# Fastino_FPGA_LVDS.net
KiCad netlist of a schematic drawn in Altium Designer
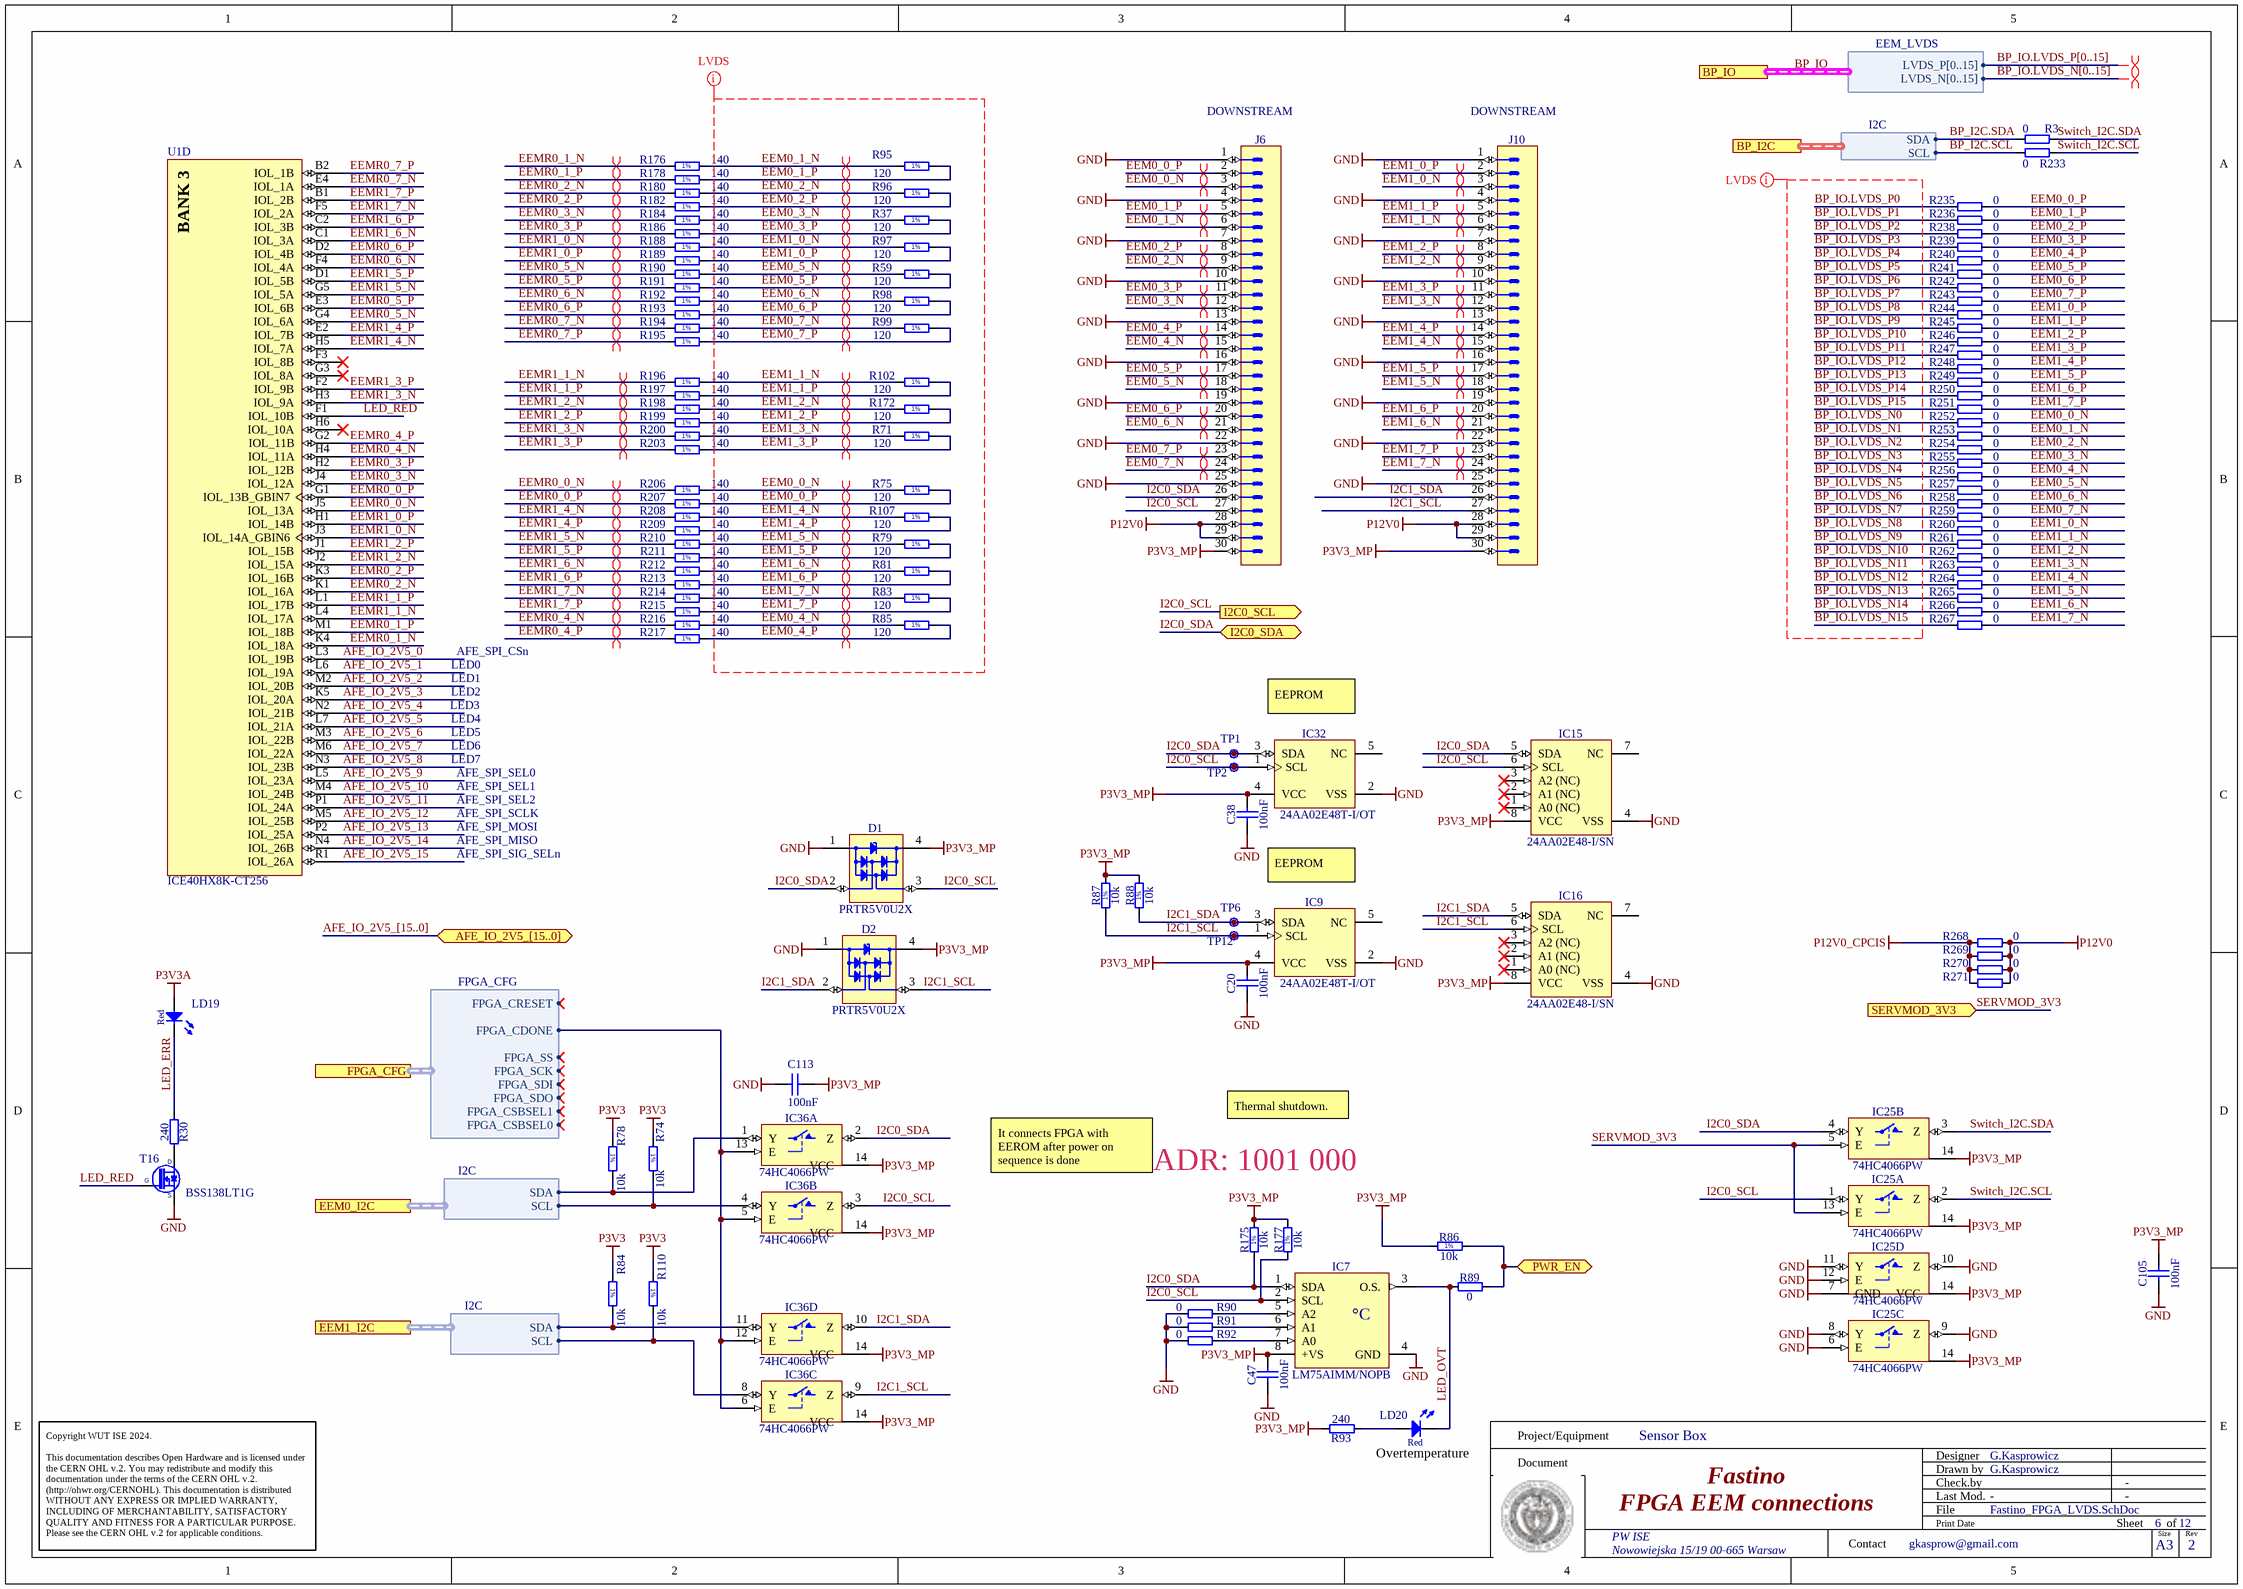
[diagram p0: Fastino_FPGA_LVDS.SchDoc]

(export (version "E")
  (design (tool "Eeschema 10.0.6"))
  (components
    (comp (ref "C20")
      (value "100nF")
      (footprint "CAPC1005X55N")
      (description "Non-polarised capacitor")
      (fields
        (field (name "PART NUMBER") "CC0402_100NF_16V_10%_X5R")
        (field (name "VOLTAGE") "16V")
        (field (name "AUTHOR") "CERN DEM JLC")
      )
      (libsource (lib "Capacitors") (part "Capacitor - non polarized"))
    )
    (comp (ref "C38")
      (value "100nF")
      (footprint "CAPC1005X55N")
      (description "Non-polarised capacitor")
      (fields
        (field (name "PART NUMBER") "CC0402_100NF_16V_10%_X5R")
        (field (name "VOLTAGE") "16V")
        (field (name "AUTHOR") "CERN DEM JLC")
      )
      (libsource (lib "Capacitors") (part "Capacitor - non polarized"))
    )
    (comp (ref "C47")
      (value "100nF")
      (footprint "CAPC1005X55N")
      (description "Non-polarised capacitor")
      (fields
        (field (name "PART NUMBER") "CC0402_100NF_16V_10%_X5R")
        (field (name "VOLTAGE") "16V")
        (field (name "AUTHOR") "CERN DEM JLC")
      )
      (libsource (lib "Capacitors") (part "Capacitor - non polarized"))
    )
    (comp (ref "C105")
      (value "100nF")
      (footprint "CAPC1005X55N")
      (description "Non-polarised capacitor")
      (fields
        (field (name "PART NUMBER") "CC0402_100NF_16V_10%_X5R")
        (field (name "VOLTAGE") "16V")
        (field (name "AUTHOR") "CERN DEM JLC")
      )
      (libsource (lib "Capacitors") (part "Capacitor - non polarized"))
    )
    (comp (ref "C113")
      (value "100nF")
      (footprint "CAPC1005X55N")
      (description "Non-polarised capacitor")
      (fields
        (field (name "PART NUMBER") "CC0402_100NF_16V_10%_X5R")
        (field (name "VOLTAGE") "16V")
        (field (name "AUTHOR") "CERN DEM JLC")
      )
      (libsource (lib "Capacitors") (part "Capacitor - non polarized"))
    )
    (comp (ref "D1")
      (value "PRTR5V0U2X")
      (footprint "SOT190P230X110-4N")
      (description "Ultra Low Capacitance Double Rail-to-Rail ESD Protection Diode")
      (fields
        (field (name "VOLTAGE") "5.5V")
        (field (name "MANUFACTURER") "NXP SEMICONDUCTORS")
        (field (name "AUTHOR") "CERN DEM JLC")
      )
      (libsource (lib "ICs And Semiconductors") (part "PRTR5V0U2X"))
    )
    (comp (ref "D2")
      (value "PRTR5V0U2X")
      (footprint "SOT190P230X110-4N")
      (description "Ultra Low Capacitance Double Rail-to-Rail ESD Protection Diode")
      (fields
        (field (name "VOLTAGE") "5.5V")
        (field (name "MANUFACTURER") "NXP SEMICONDUCTORS")
        (field (name "AUTHOR") "CERN DEM JLC")
      )
      (libsource (lib "ICs And Semiconductors") (part "PRTR5V0U2X"))
    )
    (comp (ref "IC7")
      (value "LM75AIMM/NOPB")
      (footprint "SOP65P490X109-8N")
      (description "Digital Temperature Sensor and Thermal Watchdog with Two-Wire Interface")
      (fields (field (name "MANUFACTURER") "TEXAS INSTRUMENTS") (field (name "AUTHOR") "CERN DEM JLC"))
      (libsource (lib "ICs And Semiconductors") (part "LM75"))
    )
    (comp (ref "IC9")
      (value "24AA02E48T-I/OT")
      (footprint "SOT95P280X145-5N")
      (description "1.7V-5.5V, 2K I2C Serial EEPROM With EUI-48 Node Identity")
      (fields (field (name "MANUFACTURER") "MICROCHIP TECHNOLOGY") (field (name "AUTHOR") "CERN DEM MR"))
      (libsource (lib "ICs And Semiconductors") (part "24AA02E48T-I/OT"))
    )
    (comp (ref "IC15")
      (value "24AA02E48-I/SN")
      (footprint "SOIC127P600X175-8N")
      (description "1.7V-5.5V, 2K I2C™ Serial EEPROMs with EUI-48™ Node Identity")
      (fields (field (name "MANUFACTURER") "MICROCHIP TECHNOLOGY") (field (name "AUTHOR") "CERN DEM MR"))
      (libsource (lib "ICS-logic") (part "MEM_24AA02E48-I/SN"))
    )
    (comp (ref "IC16")
      (value "24AA02E48-I/SN")
      (footprint "SOIC127P600X175-8N")
      (description "1.7V-5.5V, 2K I2C™ Serial EEPROMs with EUI-48™ Node Identity")
      (fields (field (name "MANUFACTURER") "MICROCHIP TECHNOLOGY") (field (name "AUTHOR") "CERN DEM MR"))
      (libsource (lib "ICS-logic") (part "MEM_24AA02E48-I/SN"))
    )
    (comp (ref "IC25")
      (value "74HC4066PW")
      (footprint "SOP65P640X110-14N")
      (fields (field (name "MANUFACTURER") "NXP SEMICONDUCTORS") (field (name "AUTHOR") "CERN DEM JLC"))
      (libsource (lib "ICs And Semiconductors") (part "4066"))
    )
    (comp (ref "IC32")
      (value "24AA02E48T-I/OT")
      (footprint "SOT95P280X145-5N")
      (description "1.7V-5.5V, 2K I2C Serial EEPROM With EUI-48 Node Identity")
      (fields (field (name "MANUFACTURER") "MICROCHIP TECHNOLOGY") (field (name "AUTHOR") "CERN DEM MR"))
      (libsource (lib "ICs And Semiconductors") (part "24AA02E48T-I/OT"))
    )
    (comp (ref "IC36")
      (value "74HC4066PW")
      (footprint "SOP65P640X110-14N")
      (fields (field (name "MANUFACTURER") "NXP SEMICONDUCTORS") (field (name "AUTHOR") "CERN DEM JLC"))
      (libsource (lib "ICs And Semiconductors") (part "4066"))
    )
    (comp (ref "J6")
      (value "~")
      (footprint "3M_N2530-6002RB")
      (description "Connector 30 Male")
      (fields
        (field (name "PART NUMBER") "3M_N2530-6002RB")
        (field (name "MANUFACTURER") "3M")
        (field (name "AUTHOR") "CERN DEM JLC")
      )
      (libsource (lib "Connectors") (part "Connector 30 Male"))
    )
    (comp (ref "J10")
      (value "~")
      (footprint "3M_N2530-6002RB")
      (description "Connector 30 Male")
      (fields
        (field (name "PART NUMBER") "3M_N2530-6002RB")
        (field (name "MANUFACTURER") "3M")
        (field (name "AUTHOR") "CERN DEM JLC")
      )
      (libsource (lib "Connectors") (part "Connector 30 Male"))
    )
    (comp (ref "LD19")
      (value "Red")
      (footprint "LED_AVAGO_HSMC-C120")
      (description "LED Red 1C 2A")
      (fields
        (field (name "PART NUMBER") "LED_AVAGO_HSMC-C120")
        (field (name "MANUFACTURER") "AVAGO TECHNOLOGIES")
        (field (name "AUTHOR") "CERN DEM JMW")
      )
      (libsource (lib "ICs And Semiconductors") (part "LED Red 1C 2A"))
    )
    (comp (ref "LD20")
      (value "Red")
      (footprint "LED_AVAGO_HSMC-C120")
      (description "LED Red 1C 2A")
      (fields
        (field (name "PART NUMBER") "LED_AVAGO_HSMC-C120")
        (field (name "MANUFACTURER") "AVAGO TECHNOLOGIES")
        (field (name "AUTHOR") "CERN DEM JMW")
      )
      (libsource (lib "ICs And Semiconductors") (part "LED Red 1C 2A"))
    )
    (comp (ref "R3")
      (value "0")
      (footprint "RESC1005X40N")
      (description "Resistor")
      (fields
        (field (name "PART NUMBER") "R0402_0R_JUMPER")
        (field (name "MANUFACTURER") "GENERIC")
        (field (name "AUTHOR") "CERN DEM JLC")
      )
      (libsource (lib "Resistors") (part "Resistor"))
    )
    (comp (ref "R30")
      (value "240")
      (footprint "RESC1005X40N")
      (description "Resistor - 1%")
      (fields
        (field (name "PART NUMBER") "R0402_240R_1%_0.0625W_100PPM")
        (field (name "POWER") "0.0625W")
        (field (name "AUTHOR") "CERN DEM JLC")
      )
      (libsource (lib "") (part "Resistor - 1%_1"))
    )
    (comp (ref "R37")
      (value "120")
      (footprint "RESC1005X40N")
      (description "Resistor - 1%")
      (fields
        (field (name "PART NUMBER") "R0402_120R_1%_0.0625W_100PPM")
        (field (name "POWER") "0.0625W")
        (field (name "AUTHOR") "CERN DEM JLC")
      )
      (libsource (lib "") (part "Resistor - 1%_1"))
    )
    (comp (ref "R59")
      (value "120")
      (footprint "RESC1005X40N")
      (description "Resistor - 1%")
      (fields
        (field (name "PART NUMBER") "R0402_120R_1%_0.0625W_100PPM")
        (field (name "POWER") "0.0625W")
        (field (name "AUTHOR") "CERN DEM JLC")
      )
      (libsource (lib "") (part "Resistor - 1%_1"))
    )
    (comp (ref "R71")
      (value "120")
      (footprint "RESC1005X40N")
      (description "Resistor - 1%")
      (fields
        (field (name "PART NUMBER") "R0402_120R_1%_0.0625W_100PPM")
        (field (name "POWER") "0.0625W")
        (field (name "AUTHOR") "CERN DEM JLC")
      )
      (libsource (lib "") (part "Resistor - 1%_1"))
    )
    (comp (ref "R74")
      (value "10k")
      (footprint "RESC1005X40N")
      (description "Resistor - 1%")
      (fields
        (field (name "PART NUMBER") "R0402_10K_1%_0.0625W_100PPM")
        (field (name "POWER") "0.0625W")
        (field (name "AUTHOR") "CERN DEM JLC")
      )
      (libsource (lib "") (part "Resistor - 1%_1"))
    )
    (comp (ref "R75")
      (value "120")
      (footprint "RESC1005X40N")
      (description "Resistor - 1%")
      (fields
        (field (name "PART NUMBER") "R0402_120R_1%_0.0625W_100PPM")
        (field (name "POWER") "0.0625W")
        (field (name "AUTHOR") "CERN DEM JLC")
      )
      (libsource (lib "") (part "Resistor - 1%_1"))
    )
    (comp (ref "R78")
      (value "10k")
      (footprint "RESC1005X40N")
      (description "Resistor - 1%")
      (fields
        (field (name "PART NUMBER") "R0402_10K_1%_0.0625W_100PPM")
        (field (name "POWER") "0.0625W")
        (field (name "AUTHOR") "CERN DEM JLC")
      )
      (libsource (lib "") (part "Resistor - 1%_1"))
    )
    (comp (ref "R79")
      (value "120")
      (footprint "RESC1005X40N")
      (description "Resistor - 1%")
      (fields
        (field (name "PART NUMBER") "R0402_120R_1%_0.0625W_100PPM")
        (field (name "POWER") "0.0625W")
        (field (name "AUTHOR") "CERN DEM JLC")
      )
      (libsource (lib "") (part "Resistor - 1%_1"))
    )
    (comp (ref "R81")
      (value "120")
      (footprint "RESC1005X40N")
      (description "Resistor - 1%")
      (fields
        (field (name "PART NUMBER") "R0402_120R_1%_0.0625W_100PPM")
        (field (name "POWER") "0.0625W")
        (field (name "AUTHOR") "CERN DEM JLC")
      )
      (libsource (lib "") (part "Resistor - 1%_1"))
    )
    (comp (ref "R83")
      (value "120")
      (footprint "RESC1005X40N")
      (description "Resistor - 1%")
      (fields
        (field (name "PART NUMBER") "R0402_120R_1%_0.0625W_100PPM")
        (field (name "POWER") "0.0625W")
        (field (name "AUTHOR") "CERN DEM JLC")
      )
      (libsource (lib "") (part "Resistor - 1%_1"))
    )
    (comp (ref "R84")
      (value "10k")
      (footprint "RESC1005X40N")
      (description "Resistor - 1%")
      (fields
        (field (name "PART NUMBER") "R0402_10K_1%_0.0625W_100PPM")
        (field (name "POWER") "0.0625W")
        (field (name "AUTHOR") "CERN DEM JLC")
      )
      (libsource (lib "") (part "Resistor - 1%_1"))
    )
    (comp (ref "R85")
      (value "120")
      (footprint "RESC1005X40N")
      (description "Resistor - 1%")
      (fields
        (field (name "PART NUMBER") "R0402_120R_1%_0.0625W_100PPM")
        (field (name "POWER") "0.0625W")
        (field (name "AUTHOR") "CERN DEM JLC")
      )
      (libsource (lib "") (part "Resistor - 1%_1"))
    )
    (comp (ref "R86")
      (value "10k")
      (footprint "RESC1005X40N")
      (description "Resistor - 1%")
      (fields
        (field (name "PART NUMBER") "R0402_10K_1%_0.0625W_100PPM")
        (field (name "POWER") "0.0625W")
        (field (name "AUTHOR") "CERN DEM JLC")
      )
      (libsource (lib "") (part "Resistor - 1%_1"))
    )
    (comp (ref "R87")
      (value "10k")
      (footprint "RESC1005X40N")
      (description "Resistor - 1%")
      (fields
        (field (name "PART NUMBER") "R0402_10K_1%_0.0625W_100PPM")
        (field (name "POWER") "0.0625W")
        (field (name "AUTHOR") "CERN DEM JLC")
      )
      (libsource (lib "") (part "Resistor - 1%_1"))
    )
    (comp (ref "R88")
      (value "10k")
      (footprint "RESC1005X40N")
      (description "Resistor - 1%")
      (fields
        (field (name "PART NUMBER") "R0402_10K_1%_0.0625W_100PPM")
        (field (name "POWER") "0.0625W")
        (field (name "AUTHOR") "CERN DEM JLC")
      )
      (libsource (lib "") (part "Resistor - 1%_1"))
    )
    (comp (ref "R89")
      (value "0")
      (footprint "RESC1005X40N")
      (description "Resistor")
      (fields
        (field (name "PART NUMBER") "R0402_0R_JUMPER")
        (field (name "MANUFACTURER") "GENERIC")
        (field (name "AUTHOR") "CERN DEM JLC")
      )
      (libsource (lib "Resistors") (part "Resistor"))
    )
    (comp (ref "R90")
      (value "0")
      (footprint "RESC1005X40N")
      (description "Resistor")
      (fields
        (field (name "PART NUMBER") "R0402_0R_JUMPER")
        (field (name "MANUFACTURER") "GENERIC")
        (field (name "AUTHOR") "CERN DEM JLC")
      )
      (libsource (lib "Resistors") (part "Resistor"))
    )
    (comp (ref "R91")
      (value "0")
      (footprint "RESC1005X40N")
      (description "Resistor")
      (fields
        (field (name "PART NUMBER") "R0402_0R_JUMPER")
        (field (name "MANUFACTURER") "GENERIC")
        (field (name "AUTHOR") "CERN DEM JLC")
      )
      (libsource (lib "Resistors") (part "Resistor"))
    )
    (comp (ref "R92")
      (value "0")
      (footprint "RESC1005X40N")
      (description "Resistor")
      (fields
        (field (name "PART NUMBER") "R0402_0R_JUMPER")
        (field (name "MANUFACTURER") "GENERIC")
        (field (name "AUTHOR") "CERN DEM JLC")
      )
      (libsource (lib "Resistors") (part "Resistor"))
    )
    (comp (ref "R93")
      (value "240")
      (footprint "RESC1005X40N")
      (description "Resistor - 1%")
      (fields
        (field (name "PART NUMBER") "R0402_240R_1%_0.0625W_100PPM")
        (field (name "POWER") "0.0625W")
        (field (name "AUTHOR") "CERN DEM JLC")
      )
      (libsource (lib "") (part "Resistor - 1%_1"))
    )
    (comp (ref "R95")
      (value "120")
      (footprint "RESC1005X40N")
      (description "Resistor - 1%")
      (fields
        (field (name "PART NUMBER") "R0402_120R_1%_0.0625W_100PPM")
        (field (name "POWER") "0.0625W")
        (field (name "AUTHOR") "CERN DEM JLC")
      )
      (libsource (lib "") (part "Resistor - 1%_1"))
    )
    (comp (ref "R96")
      (value "120")
      (footprint "RESC1005X40N")
      (description "Resistor - 1%")
      (fields
        (field (name "PART NUMBER") "R0402_120R_1%_0.0625W_100PPM")
        (field (name "POWER") "0.0625W")
        (field (name "AUTHOR") "CERN DEM JLC")
      )
      (libsource (lib "") (part "Resistor - 1%_1"))
    )
    (comp (ref "R97")
      (value "120")
      (footprint "RESC1005X40N")
      (description "Resistor - 1%")
      (fields
        (field (name "PART NUMBER") "R0402_120R_1%_0.0625W_100PPM")
        (field (name "POWER") "0.0625W")
        (field (name "AUTHOR") "CERN DEM JLC")
      )
      (libsource (lib "") (part "Resistor - 1%_1"))
    )
    (comp (ref "R98")
      (value "120")
      (footprint "RESC1005X40N")
      (description "Resistor - 1%")
      (fields
        (field (name "PART NUMBER") "R0402_120R_1%_0.0625W_100PPM")
        (field (name "POWER") "0.0625W")
        (field (name "AUTHOR") "CERN DEM JLC")
      )
      (libsource (lib "") (part "Resistor - 1%_1"))
    )
    (comp (ref "R99")
      (value "120")
      (footprint "RESC1005X40N")
      (description "Resistor - 1%")
      (fields
        (field (name "PART NUMBER") "R0402_120R_1%_0.0625W_100PPM")
        (field (name "POWER") "0.0625W")
        (field (name "AUTHOR") "CERN DEM JLC")
      )
      (libsource (lib "") (part "Resistor - 1%_1"))
    )
    (comp (ref "R102")
      (value "120")
      (footprint "RESC1005X40N")
      (description "Resistor - 1%")
      (fields
        (field (name "PART NUMBER") "R0402_120R_1%_0.0625W_100PPM")
        (field (name "POWER") "0.0625W")
        (field (name "AUTHOR") "CERN DEM JLC")
      )
      (libsource (lib "") (part "Resistor - 1%_1"))
    )
    (comp (ref "R107")
      (value "120")
      (footprint "RESC1005X40N")
      (description "Resistor - 1%")
      (fields
        (field (name "PART NUMBER") "R0402_120R_1%_0.0625W_100PPM")
        (field (name "POWER") "0.0625W")
        (field (name "AUTHOR") "CERN DEM JLC")
      )
      (libsource (lib "") (part "Resistor - 1%_1"))
    )
    (comp (ref "R110")
      (value "10k")
      (footprint "RESC1005X40N")
      (description "Resistor - 1%")
      (fields
        (field (name "PART NUMBER") "R0402_10K_1%_0.0625W_100PPM")
        (field (name "POWER") "0.0625W")
        (field (name "AUTHOR") "CERN DEM JLC")
      )
      (libsource (lib "") (part "Resistor - 1%_1"))
    )
    (comp (ref "R172")
      (value "120")
      (footprint "RESC1005X40N")
      (description "Resistor - 1%")
      (fields
        (field (name "PART NUMBER") "R0402_120R_1%_0.0625W_100PPM")
        (field (name "POWER") "0.0625W")
        (field (name "AUTHOR") "CERN DEM JLC")
      )
      (libsource (lib "") (part "Resistor - 1%_1"))
    )
    (comp (ref "R175")
      (value "10k")
      (footprint "RESC1005X40N")
      (description "Resistor - 1%")
      (fields
        (field (name "PART NUMBER") "R0402_10K_1%_0.0625W_100PPM")
        (field (name "POWER") "0.0625W")
        (field (name "AUTHOR") "CERN DEM JLC")
      )
      (libsource (lib "") (part "Resistor - 1%_1"))
    )
    (comp (ref "R176")
      (value "140")
      (footprint "RESC0603X28N")
      (description "Resistor - 1%")
      (fields
        (field (name "PART NUMBER") "R0201_140R_1%_0.05W_200PPM")
        (field (name "POWER") "0.05W")
        (field (name "AUTHOR") "CERN DEM MR")
      )
      (libsource (lib "Resistors") (part "Resistor - 1%"))
    )
    (comp (ref "R177")
      (value "10k")
      (footprint "RESC1005X40N")
      (description "Resistor - 1%")
      (fields
        (field (name "PART NUMBER") "R0402_10K_1%_0.0625W_100PPM")
        (field (name "POWER") "0.0625W")
        (field (name "AUTHOR") "CERN DEM JLC")
      )
      (libsource (lib "") (part "Resistor - 1%_1"))
    )
    (comp (ref "R178")
      (value "140")
      (footprint "RESC0603X28N")
      (description "Resistor - 1%")
      (fields
        (field (name "PART NUMBER") "R0201_140R_1%_0.05W_200PPM")
        (field (name "POWER") "0.05W")
        (field (name "AUTHOR") "CERN DEM MR")
      )
      (libsource (lib "Resistors") (part "Resistor - 1%"))
    )
    (comp (ref "R180")
      (value "140")
      (footprint "RESC0603X28N")
      (description "Resistor - 1%")
      (fields
        (field (name "PART NUMBER") "R0201_140R_1%_0.05W_200PPM")
        (field (name "POWER") "0.05W")
        (field (name "AUTHOR") "CERN DEM MR")
      )
      (libsource (lib "Resistors") (part "Resistor - 1%"))
    )
    (comp (ref "R182")
      (value "140")
      (footprint "RESC0603X28N")
      (description "Resistor - 1%")
      (fields
        (field (name "PART NUMBER") "R0201_140R_1%_0.05W_200PPM")
        (field (name "POWER") "0.05W")
        (field (name "AUTHOR") "CERN DEM MR")
      )
      (libsource (lib "Resistors") (part "Resistor - 1%"))
    )
    (comp (ref "R184")
      (value "140")
      (footprint "RESC0603X28N")
      (description "Resistor - 1%")
      (fields
        (field (name "PART NUMBER") "R0201_140R_1%_0.05W_200PPM")
        (field (name "POWER") "0.05W")
        (field (name "AUTHOR") "CERN DEM MR")
      )
      (libsource (lib "Resistors") (part "Resistor - 1%"))
    )
    (comp (ref "R186")
      (value "140")
      (footprint "RESC0603X28N")
      (description "Resistor - 1%")
      (fields
        (field (name "PART NUMBER") "R0201_140R_1%_0.05W_200PPM")
        (field (name "POWER") "0.05W")
        (field (name "AUTHOR") "CERN DEM MR")
      )
      (libsource (lib "Resistors") (part "Resistor - 1%"))
    )
    (comp (ref "R188")
      (value "140")
      (footprint "RESC0603X28N")
      (description "Resistor - 1%")
      (fields
        (field (name "PART NUMBER") "R0201_140R_1%_0.05W_200PPM")
        (field (name "POWER") "0.05W")
        (field (name "AUTHOR") "CERN DEM MR")
      )
      (libsource (lib "Resistors") (part "Resistor - 1%"))
    )
    (comp (ref "R189")
      (value "140")
      (footprint "RESC0603X28N")
      (description "Resistor - 1%")
      (fields
        (field (name "PART NUMBER") "R0201_140R_1%_0.05W_200PPM")
        (field (name "POWER") "0.05W")
        (field (name "AUTHOR") "CERN DEM MR")
      )
      (libsource (lib "Resistors") (part "Resistor - 1%"))
    )
    (comp (ref "R190")
      (value "140")
      (footprint "RESC0603X28N")
      (description "Resistor - 1%")
      (fields
        (field (name "PART NUMBER") "R0201_140R_1%_0.05W_200PPM")
        (field (name "POWER") "0.05W")
        (field (name "AUTHOR") "CERN DEM MR")
      )
      (libsource (lib "Resistors") (part "Resistor - 1%"))
    )
    (comp (ref "R191")
      (value "140")
      (footprint "RESC0603X28N")
      (description "Resistor - 1%")
      (fields
        (field (name "PART NUMBER") "R0201_140R_1%_0.05W_200PPM")
        (field (name "POWER") "0.05W")
        (field (name "AUTHOR") "CERN DEM MR")
      )
      (libsource (lib "Resistors") (part "Resistor - 1%"))
    )
    (comp (ref "R192")
      (value "140")
      (footprint "RESC0603X28N")
      (description "Resistor - 1%")
      (fields
        (field (name "PART NUMBER") "R0201_140R_1%_0.05W_200PPM")
        (field (name "POWER") "0.05W")
        (field (name "AUTHOR") "CERN DEM MR")
      )
      (libsource (lib "Resistors") (part "Resistor - 1%"))
    )
    (comp (ref "R193")
      (value "140")
      (footprint "RESC0603X28N")
      (description "Resistor - 1%")
      (fields
        (field (name "PART NUMBER") "R0201_140R_1%_0.05W_200PPM")
        (field (name "POWER") "0.05W")
        (field (name "AUTHOR") "CERN DEM MR")
      )
      (libsource (lib "Resistors") (part "Resistor - 1%"))
    )
    (comp (ref "R194")
      (value "140")
      (footprint "RESC0603X28N")
      (description "Resistor - 1%")
      (fields
        (field (name "PART NUMBER") "R0201_140R_1%_0.05W_200PPM")
        (field (name "POWER") "0.05W")
        (field (name "AUTHOR") "CERN DEM MR")
      )
      (libsource (lib "Resistors") (part "Resistor - 1%"))
    )
    (comp (ref "R195")
      (value "140")
      (footprint "RESC0603X28N")
      (description "Resistor - 1%")
      (fields
        (field (name "PART NUMBER") "R0201_140R_1%_0.05W_200PPM")
        (field (name "POWER") "0.05W")
        (field (name "AUTHOR") "CERN DEM MR")
      )
      (libsource (lib "Resistors") (part "Resistor - 1%"))
    )
    (comp (ref "R196")
      (value "140")
      (footprint "RESC0603X28N")
      (description "Resistor - 1%")
      (fields
        (field (name "PART NUMBER") "R0201_140R_1%_0.05W_200PPM")
        (field (name "POWER") "0.05W")
        (field (name "AUTHOR") "CERN DEM MR")
      )
      (libsource (lib "Resistors") (part "Resistor - 1%"))
    )
    (comp (ref "R197")
      (value "140")
      (footprint "RESC0603X28N")
      (description "Resistor - 1%")
      (fields
        (field (name "PART NUMBER") "R0201_140R_1%_0.05W_200PPM")
        (field (name "POWER") "0.05W")
        (field (name "AUTHOR") "CERN DEM MR")
      )
      (libsource (lib "Resistors") (part "Resistor - 1%"))
    )
    (comp (ref "R198")
      (value "140")
      (footprint "RESC0603X28N")
      (description "Resistor - 1%")
      (fields
        (field (name "PART NUMBER") "R0201_140R_1%_0.05W_200PPM")
        (field (name "POWER") "0.05W")
        (field (name "AUTHOR") "CERN DEM MR")
      )
      (libsource (lib "Resistors") (part "Resistor - 1%"))
    )
    (comp (ref "R199")
      (value "140")
      (footprint "RESC0603X28N")
      (description "Resistor - 1%")
      (fields
        (field (name "PART NUMBER") "R0201_140R_1%_0.05W_200PPM")
        (field (name "POWER") "0.05W")
        (field (name "AUTHOR") "CERN DEM MR")
      )
      (libsource (lib "Resistors") (part "Resistor - 1%"))
    )
    (comp (ref "R200")
      (value "140")
      (footprint "RESC0603X28N")
      (description "Resistor - 1%")
      (fields
        (field (name "PART NUMBER") "R0201_140R_1%_0.05W_200PPM")
        (field (name "POWER") "0.05W")
        (field (name "AUTHOR") "CERN DEM MR")
      )
      (libsource (lib "Resistors") (part "Resistor - 1%"))
    )
    (comp (ref "R203")
      (value "140")
      (footprint "RESC0603X28N")
      (description "Resistor - 1%")
      (fields
        (field (name "PART NUMBER") "R0201_140R_1%_0.05W_200PPM")
        (field (name "POWER") "0.05W")
        (field (name "AUTHOR") "CERN DEM MR")
      )
      (libsource (lib "Resistors") (part "Resistor - 1%"))
    )
    (comp (ref "R206")
      (value "140")
      (footprint "RESC0603X28N")
      (description "Resistor - 1%")
      (fields
        (field (name "PART NUMBER") "R0201_140R_1%_0.05W_200PPM")
        (field (name "POWER") "0.05W")
        (field (name "AUTHOR") "CERN DEM MR")
      )
      (libsource (lib "Resistors") (part "Resistor - 1%"))
    )
    (comp (ref "R207")
      (value "140")
      (footprint "RESC0603X28N")
      (description "Resistor - 1%")
      (fields
        (field (name "PART NUMBER") "R0201_140R_1%_0.05W_200PPM")
        (field (name "POWER") "0.05W")
        (field (name "AUTHOR") "CERN DEM MR")
      )
      (libsource (lib "Resistors") (part "Resistor - 1%"))
    )
    (comp (ref "R208")
      (value "140")
      (footprint "RESC0603X28N")
      (description "Resistor - 1%")
      (fields
        (field (name "PART NUMBER") "R0201_140R_1%_0.05W_200PPM")
        (field (name "POWER") "0.05W")
        (field (name "AUTHOR") "CERN DEM MR")
      )
      (libsource (lib "Resistors") (part "Resistor - 1%"))
    )
    (comp (ref "R209")
      (value "140")
      (footprint "RESC0603X28N")
      (description "Resistor - 1%")
      (fields
        (field (name "PART NUMBER") "R0201_140R_1%_0.05W_200PPM")
        (field (name "POWER") "0.05W")
        (field (name "AUTHOR") "CERN DEM MR")
      )
      (libsource (lib "Resistors") (part "Resistor - 1%"))
    )
    (comp (ref "R210")
      (value "140")
      (footprint "RESC0603X28N")
      (description "Resistor - 1%")
      (fields
        (field (name "PART NUMBER") "R0201_140R_1%_0.05W_200PPM")
        (field (name "POWER") "0.05W")
        (field (name "AUTHOR") "CERN DEM MR")
      )
      (libsource (lib "Resistors") (part "Resistor - 1%"))
    )
    (comp (ref "R211")
      (value "140")
      (footprint "RESC0603X28N")
      (description "Resistor - 1%")
      (fields
        (field (name "PART NUMBER") "R0201_140R_1%_0.05W_200PPM")
        (field (name "POWER") "0.05W")
        (field (name "AUTHOR") "CERN DEM MR")
      )
      (libsource (lib "Resistors") (part "Resistor - 1%"))
    )
    (comp (ref "R212")
      (value "140")
      (footprint "RESC0603X28N")
      (description "Resistor - 1%")
      (fields
        (field (name "PART NUMBER") "R0201_140R_1%_0.05W_200PPM")
        (field (name "POWER") "0.05W")
        (field (name "AUTHOR") "CERN DEM MR")
      )
      (libsource (lib "Resistors") (part "Resistor - 1%"))
    )
    (comp (ref "R213")
      (value "140")
      (footprint "RESC0603X28N")
      (description "Resistor - 1%")
      (fields
        (field (name "PART NUMBER") "R0201_140R_1%_0.05W_200PPM")
        (field (name "POWER") "0.05W")
        (field (name "AUTHOR") "CERN DEM MR")
      )
      (libsource (lib "Resistors") (part "Resistor - 1%"))
    )
    (comp (ref "R214")
      (value "140")
      (footprint "RESC0603X28N")
      (description "Resistor - 1%")
      (fields
        (field (name "PART NUMBER") "R0201_140R_1%_0.05W_200PPM")
        (field (name "POWER") "0.05W")
        (field (name "AUTHOR") "CERN DEM MR")
      )
      (libsource (lib "Resistors") (part "Resistor - 1%"))
    )
    (comp (ref "R215")
      (value "140")
      (footprint "RESC0603X28N")
      (description "Resistor - 1%")
      (fields
        (field (name "PART NUMBER") "R0201_140R_1%_0.05W_200PPM")
        (field (name "POWER") "0.05W")
        (field (name "AUTHOR") "CERN DEM MR")
      )
      (libsource (lib "Resistors") (part "Resistor - 1%"))
    )
    (comp (ref "R216")
      (value "140")
      (footprint "RESC0603X28N")
      (description "Resistor - 1%")
      (fields
        (field (name "PART NUMBER") "R0201_140R_1%_0.05W_200PPM")
        (field (name "POWER") "0.05W")
        (field (name "AUTHOR") "CERN DEM MR")
      )
      (libsource (lib "Resistors") (part "Resistor - 1%"))
    )
    (comp (ref "R217")
      (value "140")
      (footprint "RESC0603X28N")
      (description "Resistor - 1%")
      (fields
        (field (name "PART NUMBER") "R0201_140R_1%_0.05W_200PPM")
        (field (name "POWER") "0.05W")
        (field (name "AUTHOR") "CERN DEM MR")
      )
      (libsource (lib "Resistors") (part "Resistor - 1%"))
    )
    (comp (ref "R233")
      (value "0")
      (footprint "RESC1005X40N")
      (description "Resistor")
      (fields
        (field (name "PART NUMBER") "R0402_0R_JUMPER")
        (field (name "MANUFACTURER") "GENERIC")
        (field (name "AUTHOR") "CERN DEM JLC")
      )
      (libsource (lib "Resistors") (part "Resistor"))
    )
    (comp (ref "R235")
      (value "0")
      (footprint "RESC1005X40N")
      (description "Resistor")
      (fields
        (field (name "PART NUMBER") "R0402_0R_JUMPER")
        (field (name "MANUFACTURER") "GENERIC")
        (field (name "AUTHOR") "CERN DEM JLC")
      )
      (libsource (lib "Resistors") (part "Resistor"))
    )
    (comp (ref "R236")
      (value "0")
      (footprint "RESC1005X40N")
      (description "Resistor")
      (fields
        (field (name "PART NUMBER") "R0402_0R_JUMPER")
        (field (name "MANUFACTURER") "GENERIC")
        (field (name "AUTHOR") "CERN DEM JLC")
      )
      (libsource (lib "Resistors") (part "Resistor"))
    )
    (comp (ref "R238")
      (value "0")
      (footprint "RESC1005X40N")
      (description "Resistor")
      (fields
        (field (name "PART NUMBER") "R0402_0R_JUMPER")
        (field (name "MANUFACTURER") "GENERIC")
        (field (name "AUTHOR") "CERN DEM JLC")
      )
      (libsource (lib "Resistors") (part "Resistor"))
    )
    (comp (ref "R239")
      (value "0")
      (footprint "RESC1005X40N")
      (description "Resistor")
      (fields
        (field (name "PART NUMBER") "R0402_0R_JUMPER")
        (field (name "MANUFACTURER") "GENERIC")
        (field (name "AUTHOR") "CERN DEM JLC")
      )
      (libsource (lib "Resistors") (part "Resistor"))
    )
    (comp (ref "R240")
      (value "0")
      (footprint "RESC1005X40N")
      (description "Resistor")
      (fields
        (field (name "PART NUMBER") "R0402_0R_JUMPER")
        (field (name "MANUFACTURER") "GENERIC")
        (field (name "AUTHOR") "CERN DEM JLC")
      )
      (libsource (lib "Resistors") (part "Resistor"))
    )
    (comp (ref "R241")
      (value "0")
      (footprint "RESC1005X40N")
      (description "Resistor")
      (fields
        (field (name "PART NUMBER") "R0402_0R_JUMPER")
        (field (name "MANUFACTURER") "GENERIC")
        (field (name "AUTHOR") "CERN DEM JLC")
      )
      (libsource (lib "Resistors") (part "Resistor"))
    )
    (comp (ref "R242")
      (value "0")
      (footprint "RESC1005X40N")
      (description "Resistor")
      (fields
        (field (name "PART NUMBER") "R0402_0R_JUMPER")
        (field (name "MANUFACTURER") "GENERIC")
        (field (name "AUTHOR") "CERN DEM JLC")
      )
      (libsource (lib "Resistors") (part "Resistor"))
    )
    (comp (ref "R243")
      (value "0")
      (footprint "RESC1005X40N")
      (description "Resistor")
      (fields
        (field (name "PART NUMBER") "R0402_0R_JUMPER")
        (field (name "MANUFACTURER") "GENERIC")
        (field (name "AUTHOR") "CERN DEM JLC")
      )
      (libsource (lib "Resistors") (part "Resistor"))
    )
    (comp (ref "R244")
      (value "0")
      (footprint "RESC1005X40N")
      (description "Resistor")
      (fields
        (field (name "PART NUMBER") "R0402_0R_JUMPER")
        (field (name "MANUFACTURER") "GENERIC")
        (field (name "AUTHOR") "CERN DEM JLC")
      )
      (libsource (lib "Resistors") (part "Resistor"))
    )
    (comp (ref "R245")
      (value "0")
      (footprint "RESC1005X40N")
      (description "Resistor")
      (fields
        (field (name "PART NUMBER") "R0402_0R_JUMPER")
        (field (name "MANUFACTURER") "GENERIC")
        (field (name "AUTHOR") "CERN DEM JLC")
      )
      (libsource (lib "Resistors") (part "Resistor"))
    )
    (comp (ref "R246")
      (value "0")
      (footprint "RESC1005X40N")
      (description "Resistor")
      (fields
        (field (name "PART NUMBER") "R0402_0R_JUMPER")
        (field (name "MANUFACTURER") "GENERIC")
        (field (name "AUTHOR") "CERN DEM JLC")
      )
      (libsource (lib "Resistors") (part "Resistor"))
    )
    (comp (ref "R247")
      (value "0")
      (footprint "RESC1005X40N")
      (description "Resistor")
      (fields
        (field (name "PART NUMBER") "R0402_0R_JUMPER")
        (field (name "MANUFACTURER") "GENERIC")
        (field (name "AUTHOR") "CERN DEM JLC")
      )
      (libsource (lib "Resistors") (part "Resistor"))
    )
    (comp (ref "R248")
      (value "0")
      (footprint "RESC1005X40N")
      (description "Resistor")
      (fields
        (field (name "PART NUMBER") "R0402_0R_JUMPER")
        (field (name "MANUFACTURER") "GENERIC")
        (field (name "AUTHOR") "CERN DEM JLC")
      )
      (libsource (lib "Resistors") (part "Resistor"))
    )
    (comp (ref "R249")
      (value "0")
      (footprint "RESC1005X40N")
      (description "Resistor")
      (fields
        (field (name "PART NUMBER") "R0402_0R_JUMPER")
        (field (name "MANUFACTURER") "GENERIC")
        (field (name "AUTHOR") "CERN DEM JLC")
      )
      (libsource (lib "Resistors") (part "Resistor"))
    )
    (comp (ref "R250")
      (value "0")
      (footprint "RESC1005X40N")
      (description "Resistor")
      (fields
        (field (name "PART NUMBER") "R0402_0R_JUMPER")
        (field (name "MANUFACTURER") "GENERIC")
        (field (name "AUTHOR") "CERN DEM JLC")
      )
      (libsource (lib "Resistors") (part "Resistor"))
    )
    (comp (ref "R251")
      (value "0")
      (footprint "RESC0603X28N")
      (description "Resistor")
      (fields
        (field (name "PART NUMBER") "R0201_0R_JUMPER")
        (field (name "MANUFACTURER") "GENERIC")
        (field (name "AUTHOR") "CERN DEM JLC")
      )
      (libsource (lib "Resistors") (part "Resistor"))
    )
    (comp (ref "R252")
      (value "0")
      (footprint "RESC1005X40N")
      (description "Resistor")
      (fields
        (field (name "PART NUMBER") "R0402_0R_JUMPER")
        (field (name "MANUFACTURER") "GENERIC")
        (field (name "AUTHOR") "CERN DEM JLC")
      )
      (libsource (lib "Resistors") (part "Resistor"))
    )
    (comp (ref "R253")
      (value "0")
      (footprint "RESC1005X40N")
      (description "Resistor")
      (fields
        (field (name "PART NUMBER") "R0402_0R_JUMPER")
        (field (name "MANUFACTURER") "GENERIC")
        (field (name "AUTHOR") "CERN DEM JLC")
      )
      (libsource (lib "Resistors") (part "Resistor"))
    )
    (comp (ref "R254")
      (value "0")
      (footprint "RESC1005X40N")
      (description "Resistor")
      (fields
        (field (name "PART NUMBER") "R0402_0R_JUMPER")
        (field (name "MANUFACTURER") "GENERIC")
        (field (name "AUTHOR") "CERN DEM JLC")
      )
      (libsource (lib "Resistors") (part "Resistor"))
    )
    (comp (ref "R255")
      (value "0")
      (footprint "RESC1005X40N")
      (description "Resistor")
      (fields
        (field (name "PART NUMBER") "R0402_0R_JUMPER")
        (field (name "MANUFACTURER") "GENERIC")
        (field (name "AUTHOR") "CERN DEM JLC")
      )
      (libsource (lib "Resistors") (part "Resistor"))
    )
    (comp (ref "R256")
      (value "0")
      (footprint "RESC1005X40N")
      (description "Resistor")
      (fields
        (field (name "PART NUMBER") "R0402_0R_JUMPER")
        (field (name "MANUFACTURER") "GENERIC")
        (field (name "AUTHOR") "CERN DEM JLC")
      )
      (libsource (lib "Resistors") (part "Resistor"))
    )
    (comp (ref "R257")
      (value "0")
      (footprint "RESC1005X40N")
      (description "Resistor")
      (fields
        (field (name "PART NUMBER") "R0402_0R_JUMPER")
        (field (name "MANUFACTURER") "GENERIC")
        (field (name "AUTHOR") "CERN DEM JLC")
      )
      (libsource (lib "Resistors") (part "Resistor"))
    )
    (comp (ref "R258")
      (value "0")
      (footprint "RESC1005X40N")
      (description "Resistor")
      (fields
        (field (name "PART NUMBER") "R0402_0R_JUMPER")
        (field (name "MANUFACTURER") "GENERIC")
        (field (name "AUTHOR") "CERN DEM JLC")
      )
      (libsource (lib "Resistors") (part "Resistor"))
    )
    (comp (ref "R259")
      (value "0")
      (footprint "RESC1005X40N")
      (description "Resistor")
      (fields
        (field (name "PART NUMBER") "R0402_0R_JUMPER")
        (field (name "MANUFACTURER") "GENERIC")
        (field (name "AUTHOR") "CERN DEM JLC")
      )
      (libsource (lib "Resistors") (part "Resistor"))
    )
    (comp (ref "R260")
      (value "0")
      (footprint "RESC1005X40N")
      (description "Resistor")
      (fields
        (field (name "PART NUMBER") "R0402_0R_JUMPER")
        (field (name "MANUFACTURER") "GENERIC")
        (field (name "AUTHOR") "CERN DEM JLC")
      )
      (libsource (lib "Resistors") (part "Resistor"))
    )
    (comp (ref "R261")
      (value "0")
      (footprint "RESC1005X40N")
      (description "Resistor")
      (fields
        (field (name "PART NUMBER") "R0402_0R_JUMPER")
        (field (name "MANUFACTURER") "GENERIC")
        (field (name "AUTHOR") "CERN DEM JLC")
      )
      (libsource (lib "Resistors") (part "Resistor"))
    )
    (comp (ref "R262")
      (value "0")
      (footprint "RESC1005X40N")
      (description "Resistor")
      (fields
        (field (name "PART NUMBER") "R0402_0R_JUMPER")
        (field (name "MANUFACTURER") "GENERIC")
        (field (name "AUTHOR") "CERN DEM JLC")
      )
      (libsource (lib "Resistors") (part "Resistor"))
    )
    (comp (ref "R263")
      (value "0")
      (footprint "RESC1005X40N")
      (description "Resistor")
      (fields
        (field (name "PART NUMBER") "R0402_0R_JUMPER")
        (field (name "MANUFACTURER") "GENERIC")
        (field (name "AUTHOR") "CERN DEM JLC")
      )
      (libsource (lib "Resistors") (part "Resistor"))
    )
    (comp (ref "R264")
      (value "0")
      (footprint "RESC1005X40N")
      (description "Resistor")
      (fields
        (field (name "PART NUMBER") "R0402_0R_JUMPER")
        (field (name "MANUFACTURER") "GENERIC")
        (field (name "AUTHOR") "CERN DEM JLC")
      )
      (libsource (lib "Resistors") (part "Resistor"))
    )
    (comp (ref "R265")
      (value "0")
      (footprint "RESC1005X40N")
      (description "Resistor")
      (fields
        (field (name "PART NUMBER") "R0402_0R_JUMPER")
        (field (name "MANUFACTURER") "GENERIC")
        (field (name "AUTHOR") "CERN DEM JLC")
      )
      (libsource (lib "Resistors") (part "Resistor"))
    )
    (comp (ref "R266")
      (value "0")
      (footprint "RESC1005X40N")
      (description "Resistor")
      (fields
        (field (name "PART NUMBER") "R0402_0R_JUMPER")
        (field (name "MANUFACTURER") "GENERIC")
        (field (name "AUTHOR") "CERN DEM JLC")
      )
      (libsource (lib "Resistors") (part "Resistor"))
    )
    (comp (ref "R267")
      (value "0")
      (footprint "RESC0603X28N")
      (description "Resistor")
      (fields
        (field (name "PART NUMBER") "R0201_0R_JUMPER")
        (field (name "MANUFACTURER") "GENERIC")
        (field (name "AUTHOR") "CERN DEM JLC")
      )
      (libsource (lib "Resistors") (part "Resistor"))
    )
    (comp (ref "R268")
      (value "0")
      (footprint "RESC1005X40N")
      (description "Resistor")
      (fields
        (field (name "PART NUMBER") "R0402_0R_JUMPER")
        (field (name "MANUFACTURER") "GENERIC")
        (field (name "AUTHOR") "CERN DEM JLC")
      )
      (libsource (lib "Resistors") (part "Resistor"))
    )
    (comp (ref "R269")
      (value "0")
      (footprint "RESC1005X40N")
      (description "Resistor")
      (fields
        (field (name "PART NUMBER") "R0402_0R_JUMPER")
        (field (name "MANUFACTURER") "GENERIC")
        (field (name "AUTHOR") "CERN DEM JLC")
      )
      (libsource (lib "Resistors") (part "Resistor"))
    )
    (comp (ref "R270")
      (value "0")
      (footprint "RESC1005X40N")
      (description "Resistor")
      (fields
        (field (name "PART NUMBER") "R0402_0R_JUMPER")
        (field (name "MANUFACTURER") "GENERIC")
        (field (name "AUTHOR") "CERN DEM JLC")
      )
      (libsource (lib "Resistors") (part "Resistor"))
    )
    (comp (ref "R271")
      (value "0")
      (footprint "RESC1005X40N")
      (description "Resistor")
      (fields
        (field (name "PART NUMBER") "R0402_0R_JUMPER")
        (field (name "MANUFACTURER") "GENERIC")
        (field (name "AUTHOR") "CERN DEM JLC")
      )
      (libsource (lib "Resistors") (part "Resistor"))
    )
    (comp (ref "T16")
      (value "BSS138LT1G")
      (footprint "SOT95P240X110-3N")
      (description "N-CHANNEL MOSFET WITH DIODE")
      (fields (field (name "MANUFACTURER") "ON SEMICONDUCTOR") (field (name "AUTHOR") "CERN DEM JLC"))
      (libsource (lib "ICs And Semiconductors") (part "N-MOSFET-D 1G 2S 3D"))
    )
    (comp (ref "TP1")
      (value "Test Point")
      (footprint "TPS127")
      (fields (field (name "PART NUMBER") "SMD_PAD_1.27X1.27MM") (field (name "AUTHOR") "CERN DEM JLC"))
      (libsource (lib "Eletro-mechanical") (part "Test Point"))
    )
    (comp (ref "TP2")
      (value "Test Point")
      (footprint "TPS127")
      (fields (field (name "PART NUMBER") "SMD_PAD_1.27X1.27MM") (field (name "AUTHOR") "CERN DEM JLC"))
      (libsource (lib "Eletro-mechanical") (part "Test Point"))
    )
    (comp (ref "TP6")
      (value "Test Point")
      (footprint "TPS127")
      (fields (field (name "PART NUMBER") "SMD_PAD_1.27X1.27MM") (field (name "AUTHOR") "CERN DEM JLC"))
      (libsource (lib "Eletro-mechanical") (part "Test Point"))
    )
    (comp (ref "TP12")
      (value "Test Point")
      (footprint "TPS127")
      (fields (field (name "PART NUMBER") "SMD_PAD_1.27X1.27MM") (field (name "AUTHOR") "CERN DEM JLC"))
      (libsource (lib "Eletro-mechanical") (part "Test Point"))
    )
    (comp (ref "U1")
      (value "ICE40HX8K-CT256")
      (footprint "LATC-caBGA-256")
      (fields (field (name "MANUFACTURER") "Lattice Semiconductor"))
      (libsource (lib "Altium Content Vault") (part "LATC-HX8K-caBGA-256"))
    )
  )
  (nets
    (net (code "4") (name "/AFE_IO_2V5_0") (class "Default")
      (node (ref "U1") (pin "L3") (pinfunction "IOL_19B_L3") (pintype "bidirectional"))
    )
    (net (code "5") (name "/AFE_IO_2V5_1") (class "Default")
      (node (ref "U1") (pin "L6") (pinfunction "IOL_19A_L6") (pintype "bidirectional"))
    )
    (net (code "6") (name "/AFE_IO_2V5_2") (class "Default")
      (node (ref "U1") (pin "M2") (pinfunction "IOL_20B_M2") (pintype "bidirectional"))
    )
    (net (code "7") (name "/AFE_IO_2V5_3") (class "Default")
      (node (ref "U1") (pin "K5") (pinfunction "IOL_20A_K5") (pintype "bidirectional"))
    )
    (net (code "8") (name "/AFE_IO_2V5_4") (class "Default")
      (node (ref "U1") (pin "N2") (pinfunction "IOL_21B_N2") (pintype "bidirectional"))
    )
    (net (code "9") (name "/AFE_IO_2V5_5") (class "Default")
      (node (ref "U1") (pin "L7") (pinfunction "IOL_21A_L7") (pintype "bidirectional"))
    )
    (net (code "10") (name "/AFE_IO_2V5_6") (class "Default")
      (node (ref "U1") (pin "M3") (pinfunction "IOL_22B_M3") (pintype "bidirectional"))
    )
    (net (code "11") (name "/AFE_IO_2V5_7") (class "Default")
      (node (ref "U1") (pin "M6") (pinfunction "IOL_22A_M6") (pintype "bidirectional"))
    )
    (net (code "12") (name "/AFE_IO_2V5_8") (class "Default")
      (node (ref "U1") (pin "N3") (pinfunction "IOL_23B_N3") (pintype "bidirectional"))
    )
    (net (code "13") (name "/AFE_IO_2V5_9") (class "Default")
      (node (ref "U1") (pin "L5") (pinfunction "IOL_23A_L5") (pintype "bidirectional"))
    )
    (net (code "14") (name "/AFE_IO_2V5_10") (class "Default")
      (node (ref "U1") (pin "M4") (pinfunction "IOL_24B_M4") (pintype "bidirectional"))
    )
    (net (code "15") (name "/AFE_IO_2V5_11") (class "Default")
      (node (ref "U1") (pin "P1") (pinfunction "IOL_24A_P1") (pintype "bidirectional"))
    )
    (net (code "16") (name "/AFE_IO_2V5_12") (class "Default")
      (node (ref "U1") (pin "M5") (pinfunction "IOL_25B_M5") (pintype "bidirectional"))
    )
    (net (code "17") (name "/AFE_IO_2V5_13") (class "Default")
      (node (ref "U1") (pin "P2") (pinfunction "IOL_25A_P2") (pintype "bidirectional"))
    )
    (net (code "18") (name "/AFE_IO_2V5_14") (class "Default")
      (node (ref "U1") (pin "N4") (pinfunction "IOL_26B_N4") (pintype "bidirectional"))
    )
    (net (code "19") (name "/AFE_IO_2V5_15") (class "Default")
      (node (ref "U1") (pin "R1") (pinfunction "IOL_26A_R1") (pintype "bidirectional"))
    )
    (net (code "21") (name "/BP_I2C.SCL") (class "Default")
      (node (ref "R233") (pin "1") (pinfunction "1_1") (pintype "passive"))
    )
    (net (code "22") (name "/BP_I2C.SDA") (class "Default")
      (node (ref "R3") (pin "1") (pinfunction "1_1") (pintype "passive"))
    )
    (net (code "23") (name "/BP_IO.LVDS_N0") (class "Default")
      (node (ref "R252") (pin "1") (pinfunction "1_1") (pintype "passive"))
    )
    (net (code "24") (name "/BP_IO.LVDS_N1") (class "Default")
      (node (ref "R253") (pin "1") (pinfunction "1_1") (pintype "passive"))
    )
    (net (code "25") (name "/BP_IO.LVDS_N2") (class "Default")
      (node (ref "R254") (pin "1") (pinfunction "1_1") (pintype "passive"))
    )
    (net (code "26") (name "/BP_IO.LVDS_N3") (class "Default")
      (node (ref "R255") (pin "1") (pinfunction "1_1") (pintype "passive"))
    )
    (net (code "27") (name "/BP_IO.LVDS_N4") (class "Default")
      (node (ref "R256") (pin "1") (pinfunction "1_1") (pintype "passive"))
    )
    (net (code "28") (name "/BP_IO.LVDS_N5") (class "Default")
      (node (ref "R257") (pin "1") (pinfunction "1_1") (pintype "passive"))
    )
    (net (code "29") (name "/BP_IO.LVDS_N6") (class "Default")
      (node (ref "R258") (pin "1") (pinfunction "1_1") (pintype "passive"))
    )
    (net (code "30") (name "/BP_IO.LVDS_N7") (class "Default")
      (node (ref "R259") (pin "1") (pinfunction "1_1") (pintype "passive"))
    )
    (net (code "31") (name "/BP_IO.LVDS_N8") (class "Default")
      (node (ref "R260") (pin "1") (pinfunction "1_1") (pintype "passive"))
    )
    (net (code "32") (name "/BP_IO.LVDS_N9") (class "Default")
      (node (ref "R261") (pin "1") (pinfunction "1_1") (pintype "passive"))
    )
    (net (code "33") (name "/BP_IO.LVDS_N10") (class "Default")
      (node (ref "R262") (pin "1") (pinfunction "1_1") (pintype "passive"))
    )
    (net (code "34") (name "/BP_IO.LVDS_N11") (class "Default")
      (node (ref "R263") (pin "1") (pinfunction "1_1") (pintype "passive"))
    )
    (net (code "35") (name "/BP_IO.LVDS_N12") (class "Default")
      (node (ref "R264") (pin "1") (pinfunction "1_1") (pintype "passive"))
    )
    (net (code "36") (name "/BP_IO.LVDS_N13") (class "Default")
      (node (ref "R265") (pin "1") (pinfunction "1_1") (pintype "passive"))
    )
    (net (code "37") (name "/BP_IO.LVDS_N14") (class "Default")
      (node (ref "R266") (pin "1") (pinfunction "1_1") (pintype "passive"))
    )
    (net (code "38") (name "/BP_IO.LVDS_N15") (class "Default")
      (node (ref "R267") (pin "2") (pinfunction "2_2") (pintype "passive"))
    )
    (net (code "40") (name "/BP_IO.LVDS_P0") (class "Default")
      (node (ref "R235") (pin "1") (pinfunction "1_1") (pintype "passive"))
    )
    (net (code "41") (name "/BP_IO.LVDS_P1") (class "Default")
      (node (ref "R236") (pin "1") (pinfunction "1_1") (pintype "passive"))
    )
    (net (code "42") (name "/BP_IO.LVDS_P2") (class "Default")
      (node (ref "R238") (pin "1") (pinfunction "1_1") (pintype "passive"))
    )
    (net (code "43") (name "/BP_IO.LVDS_P3") (class "Default")
      (node (ref "R239") (pin "1") (pinfunction "1_1") (pintype "passive"))
    )
    (net (code "44") (name "/BP_IO.LVDS_P4") (class "Default")
      (node (ref "R240") (pin "1") (pinfunction "1_1") (pintype "passive"))
    )
    (net (code "45") (name "/BP_IO.LVDS_P5") (class "Default")
      (node (ref "R241") (pin "1") (pinfunction "1_1") (pintype "passive"))
    )
    (net (code "46") (name "/BP_IO.LVDS_P6") (class "Default")
      (node (ref "R242") (pin "1") (pinfunction "1_1") (pintype "passive"))
    )
    (net (code "47") (name "/BP_IO.LVDS_P7") (class "Default")
      (node (ref "R243") (pin "1") (pinfunction "1_1") (pintype "passive"))
    )
    (net (code "48") (name "/BP_IO.LVDS_P8") (class "Default")
      (node (ref "R244") (pin "1") (pinfunction "1_1") (pintype "passive"))
    )
    (net (code "49") (name "/BP_IO.LVDS_P9") (class "Default")
      (node (ref "R245") (pin "1") (pinfunction "1_1") (pintype "passive"))
    )
    (net (code "50") (name "/BP_IO.LVDS_P10") (class "Default")
      (node (ref "R246") (pin "1") (pinfunction "1_1") (pintype "passive"))
    )
    (net (code "51") (name "/BP_IO.LVDS_P11") (class "Default")
      (node (ref "R247") (pin "1") (pinfunction "1_1") (pintype "passive"))
    )
    (net (code "52") (name "/BP_IO.LVDS_P12") (class "Default")
      (node (ref "R248") (pin "1") (pinfunction "1_1") (pintype "passive"))
    )
    (net (code "53") (name "/BP_IO.LVDS_P13") (class "Default")
      (node (ref "R249") (pin "1") (pinfunction "1_1") (pintype "passive"))
    )
    (net (code "54") (name "/BP_IO.LVDS_P14") (class "Default")
      (node (ref "R250") (pin "1") (pinfunction "1_1") (pintype "passive"))
    )
    (net (code "55") (name "/BP_IO.LVDS_P15") (class "Default")
      (node (ref "R251") (pin "2") (pinfunction "2_2") (pintype "passive"))
    )
    (net (code "56") (name "/EEM0_0_N") (class "Default")
      (node (ref "J6") (pin "3") (pinfunction "3_3") (pintype "bidirectional"))
      (node (ref "R206") (pin "2") (pinfunction "2_2") (pintype "passive"))
      (node (ref "R252") (pin "2") (pinfunction "2_2") (pintype "passive"))
      (node (ref "R75") (pin "1") (pinfunction "1_1") (pintype "passive"))
    )
    (net (code "57") (name "/EEM0_0_P") (class "Default")
      (node (ref "J6") (pin "2") (pinfunction "2_2") (pintype "bidirectional"))
      (node (ref "R207") (pin "2") (pinfunction "2_2") (pintype "passive"))
      (node (ref "R235") (pin "2") (pinfunction "2_2") (pintype "passive"))
      (node (ref "R75") (pin "2") (pinfunction "2_2") (pintype "passive"))
    )
    (net (code "58") (name "/EEM0_1_N") (class "Default")
      (node (ref "J6") (pin "6") (pinfunction "6_6") (pintype "bidirectional"))
      (node (ref "R176") (pin "2") (pinfunction "2_2") (pintype "passive"))
      (node (ref "R253") (pin "2") (pinfunction "2_2") (pintype "passive"))
      (node (ref "R95") (pin "1") (pinfunction "1_1") (pintype "passive"))
    )
    (net (code "59") (name "/EEM0_1_P") (class "Default")
      (node (ref "J6") (pin "5") (pinfunction "5_5") (pintype "bidirectional"))
      (node (ref "R178") (pin "2") (pinfunction "2_2") (pintype "passive"))
      (node (ref "R236") (pin "2") (pinfunction "2_2") (pintype "passive"))
      (node (ref "R95") (pin "2") (pinfunction "2_2") (pintype "passive"))
    )
    (net (code "60") (name "/EEM0_2_N") (class "Default")
      (node (ref "J6") (pin "9") (pinfunction "9_9") (pintype "bidirectional"))
      (node (ref "R180") (pin "2") (pinfunction "2_2") (pintype "passive"))
      (node (ref "R254") (pin "2") (pinfunction "2_2") (pintype "passive"))
      (node (ref "R96") (pin "1") (pinfunction "1_1") (pintype "passive"))
    )
    (net (code "61") (name "/EEM0_2_P") (class "Default")
      (node (ref "J6") (pin "8") (pinfunction "8_8") (pintype "bidirectional"))
      (node (ref "R182") (pin "2") (pinfunction "2_2") (pintype "passive"))
      (node (ref "R238") (pin "2") (pinfunction "2_2") (pintype "passive"))
      (node (ref "R96") (pin "2") (pinfunction "2_2") (pintype "passive"))
    )
    (net (code "62") (name "/EEM0_3_N") (class "Default")
      (node (ref "J6") (pin "12") (pinfunction "12_12") (pintype "bidirectional"))
      (node (ref "R184") (pin "2") (pinfunction "2_2") (pintype "passive"))
      (node (ref "R255") (pin "2") (pinfunction "2_2") (pintype "passive"))
      (node (ref "R37") (pin "1") (pinfunction "1_1") (pintype "passive"))
    )
    (net (code "63") (name "/EEM0_3_P") (class "Default")
      (node (ref "J6") (pin "11") (pinfunction "11_11") (pintype "bidirectional"))
      (node (ref "R186") (pin "2") (pinfunction "2_2") (pintype "passive"))
      (node (ref "R239") (pin "2") (pinfunction "2_2") (pintype "passive"))
      (node (ref "R37") (pin "2") (pinfunction "2_2") (pintype "passive"))
    )
    (net (code "64") (name "/EEM0_4_N") (class "Default")
      (node (ref "J6") (pin "15") (pinfunction "15_15") (pintype "bidirectional"))
      (node (ref "R216") (pin "2") (pinfunction "2_2") (pintype "passive"))
      (node (ref "R256") (pin "2") (pinfunction "2_2") (pintype "passive"))
      (node (ref "R85") (pin "1") (pinfunction "1_1") (pintype "passive"))
    )
    (net (code "65") (name "/EEM0_4_P") (class "Default")
      (node (ref "J6") (pin "14") (pinfunction "14_14") (pintype "bidirectional"))
      (node (ref "R217") (pin "2") (pinfunction "2_2") (pintype "passive"))
      (node (ref "R240") (pin "2") (pinfunction "2_2") (pintype "passive"))
      (node (ref "R85") (pin "2") (pinfunction "2_2") (pintype "passive"))
    )
    (net (code "66") (name "/EEM0_5_N") (class "Default")
      (node (ref "J6") (pin "18") (pinfunction "18_18") (pintype "bidirectional"))
      (node (ref "R190") (pin "2") (pinfunction "2_2") (pintype "passive"))
      (node (ref "R257") (pin "2") (pinfunction "2_2") (pintype "passive"))
      (node (ref "R59") (pin "1") (pinfunction "1_1") (pintype "passive"))
    )
    (net (code "67") (name "/EEM0_5_P") (class "Default")
      (node (ref "J6") (pin "17") (pinfunction "17_17") (pintype "bidirectional"))
      (node (ref "R191") (pin "2") (pinfunction "2_2") (pintype "passive"))
      (node (ref "R241") (pin "2") (pinfunction "2_2") (pintype "passive"))
      (node (ref "R59") (pin "2") (pinfunction "2_2") (pintype "passive"))
    )
    (net (code "68") (name "/EEM0_6_N") (class "Default")
      (node (ref "J6") (pin "21") (pinfunction "21_21") (pintype "bidirectional"))
      (node (ref "R192") (pin "2") (pinfunction "2_2") (pintype "passive"))
      (node (ref "R258") (pin "2") (pinfunction "2_2") (pintype "passive"))
      (node (ref "R98") (pin "1") (pinfunction "1_1") (pintype "passive"))
    )
    (net (code "69") (name "/EEM0_6_P") (class "Default")
      (node (ref "J6") (pin "20") (pinfunction "20_20") (pintype "bidirectional"))
      (node (ref "R193") (pin "2") (pinfunction "2_2") (pintype "passive"))
      (node (ref "R242") (pin "2") (pinfunction "2_2") (pintype "passive"))
      (node (ref "R98") (pin "2") (pinfunction "2_2") (pintype "passive"))
    )
    (net (code "70") (name "/EEM0_7_N") (class "Default")
      (node (ref "J6") (pin "24") (pinfunction "24_24") (pintype "bidirectional"))
      (node (ref "R194") (pin "2") (pinfunction "2_2") (pintype "passive"))
      (node (ref "R259") (pin "2") (pinfunction "2_2") (pintype "passive"))
      (node (ref "R99") (pin "1") (pinfunction "1_1") (pintype "passive"))
    )
    (net (code "71") (name "/EEM0_7_P") (class "Default")
      (node (ref "J6") (pin "23") (pinfunction "23_23") (pintype "bidirectional"))
      (node (ref "R195") (pin "2") (pinfunction "2_2") (pintype "passive"))
      (node (ref "R243") (pin "2") (pinfunction "2_2") (pintype "passive"))
      (node (ref "R99") (pin "2") (pinfunction "2_2") (pintype "passive"))
    )
    (net (code "72") (name "/EEM1_0_N") (class "Default")
      (node (ref "J10") (pin "3") (pinfunction "3_3") (pintype "bidirectional"))
      (node (ref "R188") (pin "2") (pinfunction "2_2") (pintype "passive"))
      (node (ref "R260") (pin "2") (pinfunction "2_2") (pintype "passive"))
      (node (ref "R97") (pin "1") (pinfunction "1_1") (pintype "passive"))
    )
    (net (code "73") (name "/EEM1_0_P") (class "Default")
      (node (ref "J10") (pin "2") (pinfunction "2_2") (pintype "bidirectional"))
      (node (ref "R189") (pin "2") (pinfunction "2_2") (pintype "passive"))
      (node (ref "R244") (pin "2") (pinfunction "2_2") (pintype "passive"))
      (node (ref "R97") (pin "2") (pinfunction "2_2") (pintype "passive"))
    )
    (net (code "74") (name "/EEM1_1_N") (class "Default")
      (node (ref "J10") (pin "6") (pinfunction "6_6") (pintype "bidirectional"))
      (node (ref "R102") (pin "1") (pinfunction "1_1") (pintype "passive"))
      (node (ref "R196") (pin "2") (pinfunction "2_2") (pintype "passive"))
      (node (ref "R261") (pin "2") (pinfunction "2_2") (pintype "passive"))
    )
    (net (code "75") (name "/EEM1_1_P") (class "Default")
      (node (ref "J10") (pin "5") (pinfunction "5_5") (pintype "bidirectional"))
      (node (ref "R102") (pin "2") (pinfunction "2_2") (pintype "passive"))
      (node (ref "R197") (pin "2") (pinfunction "2_2") (pintype "passive"))
      (node (ref "R245") (pin "2") (pinfunction "2_2") (pintype "passive"))
    )
    (net (code "76") (name "/EEM1_2_N") (class "Default")
      (node (ref "J10") (pin "9") (pinfunction "9_9") (pintype "bidirectional"))
      (node (ref "R172") (pin "1") (pinfunction "1_1") (pintype "passive"))
      (node (ref "R198") (pin "2") (pinfunction "2_2") (pintype "passive"))
      (node (ref "R262") (pin "2") (pinfunction "2_2") (pintype "passive"))
    )
    (net (code "77") (name "/EEM1_2_P") (class "Default")
      (node (ref "J10") (pin "8") (pinfunction "8_8") (pintype "bidirectional"))
      (node (ref "R172") (pin "2") (pinfunction "2_2") (pintype "passive"))
      (node (ref "R199") (pin "2") (pinfunction "2_2") (pintype "passive"))
      (node (ref "R246") (pin "2") (pinfunction "2_2") (pintype "passive"))
    )
    (net (code "78") (name "/EEM1_3_N") (class "Default")
      (node (ref "J10") (pin "12") (pinfunction "12_12") (pintype "bidirectional"))
      (node (ref "R200") (pin "2") (pinfunction "2_2") (pintype "passive"))
      (node (ref "R263") (pin "2") (pinfunction "2_2") (pintype "passive"))
      (node (ref "R71") (pin "1") (pinfunction "1_1") (pintype "passive"))
    )
    (net (code "79") (name "/EEM1_3_P") (class "Default")
      (node (ref "J10") (pin "11") (pinfunction "11_11") (pintype "bidirectional"))
      (node (ref "R203") (pin "2") (pinfunction "2_2") (pintype "passive"))
      (node (ref "R247") (pin "2") (pinfunction "2_2") (pintype "passive"))
      (node (ref "R71") (pin "2") (pinfunction "2_2") (pintype "passive"))
    )
    (net (code "80") (name "/EEM1_4_N") (class "Default")
      (node (ref "J10") (pin "15") (pinfunction "15_15") (pintype "bidirectional"))
      (node (ref "R107") (pin "1") (pinfunction "1_1") (pintype "passive"))
      (node (ref "R208") (pin "2") (pinfunction "2_2") (pintype "passive"))
      (node (ref "R264") (pin "2") (pinfunction "2_2") (pintype "passive"))
    )
    (net (code "81") (name "/EEM1_4_P") (class "Default")
      (node (ref "J10") (pin "14") (pinfunction "14_14") (pintype "bidirectional"))
      (node (ref "R107") (pin "2") (pinfunction "2_2") (pintype "passive"))
      (node (ref "R209") (pin "2") (pinfunction "2_2") (pintype "passive"))
      (node (ref "R248") (pin "2") (pinfunction "2_2") (pintype "passive"))
    )
    (net (code "82") (name "/EEM1_5_N") (class "Default")
      (node (ref "J10") (pin "18") (pinfunction "18_18") (pintype "bidirectional"))
      (node (ref "R210") (pin "2") (pinfunction "2_2") (pintype "passive"))
      (node (ref "R265") (pin "2") (pinfunction "2_2") (pintype "passive"))
      (node (ref "R79") (pin "1") (pinfunction "1_1") (pintype "passive"))
    )
    (net (code "83") (name "/EEM1_5_P") (class "Default")
      (node (ref "J10") (pin "17") (pinfunction "17_17") (pintype "bidirectional"))
      (node (ref "R211") (pin "2") (pinfunction "2_2") (pintype "passive"))
      (node (ref "R249") (pin "2") (pinfunction "2_2") (pintype "passive"))
      (node (ref "R79") (pin "2") (pinfunction "2_2") (pintype "passive"))
    )
    (net (code "84") (name "/EEM1_6_N") (class "Default")
      (node (ref "J10") (pin "21") (pinfunction "21_21") (pintype "bidirectional"))
      (node (ref "R212") (pin "2") (pinfunction "2_2") (pintype "passive"))
      (node (ref "R266") (pin "2") (pinfunction "2_2") (pintype "passive"))
      (node (ref "R81") (pin "1") (pinfunction "1_1") (pintype "passive"))
    )
    (net (code "85") (name "/EEM1_6_P") (class "Default")
      (node (ref "J10") (pin "20") (pinfunction "20_20") (pintype "bidirectional"))
      (node (ref "R213") (pin "2") (pinfunction "2_2") (pintype "passive"))
      (node (ref "R250") (pin "2") (pinfunction "2_2") (pintype "passive"))
      (node (ref "R81") (pin "2") (pinfunction "2_2") (pintype "passive"))
    )
    (net (code "86") (name "/EEM1_7_N") (class "Default")
      (node (ref "J10") (pin "24") (pinfunction "24_24") (pintype "bidirectional"))
      (node (ref "R214") (pin "2") (pinfunction "2_2") (pintype "passive"))
      (node (ref "R267") (pin "1") (pinfunction "1_1") (pintype "passive"))
      (node (ref "R83") (pin "1") (pinfunction "1_1") (pintype "passive"))
    )
    (net (code "87") (name "/EEM1_7_P") (class "Default")
      (node (ref "J10") (pin "23") (pinfunction "23_23") (pintype "bidirectional"))
      (node (ref "R215") (pin "2") (pinfunction "2_2") (pintype "passive"))
      (node (ref "R251") (pin "1") (pinfunction "1_1") (pintype "passive"))
      (node (ref "R83") (pin "2") (pinfunction "2_2") (pintype "passive"))
    )
    (net (code "88") (name "/EEMR0_0_N") (class "Default")
      (node (ref "R206") (pin "1") (pinfunction "1_1") (pintype "passive"))
      (node (ref "U1") (pin "J5") (pinfunction "IOL_13A_J5") (pintype "bidirectional"))
    )
    (net (code "89") (name "/EEMR0_0_P") (class "Default")
      (node (ref "R207") (pin "1") (pinfunction "1_1") (pintype "passive"))
      (node (ref "U1") (pin "G1") (pinfunction "IOL_13B_GBIN7_G1") (pintype "bidirectional"))
    )
    (net (code "90") (name "/EEMR0_1_N") (class "Default")
      (node (ref "R176") (pin "1") (pinfunction "1_1") (pintype "passive"))
      (node (ref "U1") (pin "K4") (pinfunction "IOL_18A_K4") (pintype "bidirectional"))
    )
    (net (code "91") (name "/EEMR0_1_P") (class "Default")
      (node (ref "R178") (pin "1") (pinfunction "1_1") (pintype "passive"))
      (node (ref "U1") (pin "M1") (pinfunction "IOL_18B_M1") (pintype "bidirectional"))
    )
    (net (code "92") (name "/EEMR0_2_N") (class "Default")
      (node (ref "R180") (pin "1") (pinfunction "1_1") (pintype "passive"))
      (node (ref "U1") (pin "K1") (pinfunction "IOL_16A_K1") (pintype "bidirectional"))
    )
    (net (code "93") (name "/EEMR0_2_P") (class "Default")
      (node (ref "R182") (pin "1") (pinfunction "1_1") (pintype "passive"))
      (node (ref "U1") (pin "K3") (pinfunction "IOL_16B_K3") (pintype "bidirectional"))
    )
    (net (code "94") (name "/EEMR0_3_N") (class "Default")
      (node (ref "R184") (pin "1") (pinfunction "1_1") (pintype "passive"))
      (node (ref "U1") (pin "J4") (pinfunction "IOL_12A_J4") (pintype "bidirectional"))
    )
    (net (code "95") (name "/EEMR0_3_P") (class "Default")
      (node (ref "R186") (pin "1") (pinfunction "1_1") (pintype "passive"))
      (node (ref "U1") (pin "H2") (pinfunction "IOL_12B_H2") (pintype "bidirectional"))
    )
    (net (code "96") (name "/EEMR0_4_N") (class "Default")
      (node (ref "R216") (pin "1") (pinfunction "1_1") (pintype "passive"))
      (node (ref "U1") (pin "H4") (pinfunction "IOL_11A_H4") (pintype "bidirectional"))
    )
    (net (code "97") (name "/EEMR0_4_P") (class "Default")
      (node (ref "R217") (pin "1") (pinfunction "1_1") (pintype "passive"))
      (node (ref "U1") (pin "G2") (pinfunction "IOL_11B_G2") (pintype "bidirectional"))
    )
    (net (code "98") (name "/EEMR0_5_N") (class "Default")
      (node (ref "R190") (pin "1") (pinfunction "1_1") (pintype "passive"))
      (node (ref "U1") (pin "G4") (pinfunction "IOL_6A_G4") (pintype "bidirectional"))
    )
    (net (code "99") (name "/EEMR0_5_P") (class "Default")
      (node (ref "R191") (pin "1") (pinfunction "1_1") (pintype "passive"))
      (node (ref "U1") (pin "E3") (pinfunction "IOL_6B_E3") (pintype "bidirectional"))
    )
    (net (code "100") (name "/EEMR0_6_N") (class "Default")
      (node (ref "R192") (pin "1") (pinfunction "1_1") (pintype "passive"))
      (node (ref "U1") (pin "F4") (pinfunction "IOL_4A_F4") (pintype "bidirectional"))
    )
    (net (code "101") (name "/EEMR0_6_P") (class "Default")
      (node (ref "R193") (pin "1") (pinfunction "1_1") (pintype "passive"))
      (node (ref "U1") (pin "D2") (pinfunction "IOL_4B_D2") (pintype "bidirectional"))
    )
    (net (code "102") (name "/EEMR0_7_N") (class "Default")
      (node (ref "R194") (pin "1") (pinfunction "1_1") (pintype "passive"))
      (node (ref "U1") (pin "E4") (pinfunction "IOL_1A_E4") (pintype "bidirectional"))
    )
    (net (code "103") (name "/EEMR0_7_P") (class "Default")
      (node (ref "R195") (pin "1") (pinfunction "1_1") (pintype "passive"))
      (node (ref "U1") (pin "B2") (pinfunction "IOL_1B_B2") (pintype "bidirectional"))
    )
    (net (code "104") (name "/EEMR1_0_N") (class "Default")
      (node (ref "R188") (pin "1") (pinfunction "1_1") (pintype "passive"))
      (node (ref "U1") (pin "J3") (pinfunction "IOL_14A_GBIN6_J3") (pintype "bidirectional"))
    )
    (net (code "105") (name "/EEMR1_0_P") (class "Default")
      (node (ref "R189") (pin "1") (pinfunction "1_1") (pintype "passive"))
      (node (ref "U1") (pin "H1") (pinfunction "IOL_14B_H1") (pintype "bidirectional"))
    )
    (net (code "106") (name "/EEMR1_1_N") (class "Default")
      (node (ref "R196") (pin "1") (pinfunction "1_1") (pintype "passive"))
      (node (ref "U1") (pin "L4") (pinfunction "IOL_17A_L4") (pintype "bidirectional"))
    )
    (net (code "107") (name "/EEMR1_1_P") (class "Default")
      (node (ref "R197") (pin "1") (pinfunction "1_1") (pintype "passive"))
      (node (ref "U1") (pin "L1") (pinfunction "IOL_17B_L1") (pintype "bidirectional"))
    )
    (net (code "108") (name "/EEMR1_2_N") (class "Default")
      (node (ref "R198") (pin "1") (pinfunction "1_1") (pintype "passive"))
      (node (ref "U1") (pin "J2") (pinfunction "IOL_15A_J2") (pintype "bidirectional"))
    )
    (net (code "109") (name "/EEMR1_2_P") (class "Default")
      (node (ref "R199") (pin "1") (pinfunction "1_1") (pintype "passive"))
      (node (ref "U1") (pin "J1") (pinfunction "IOL_15B_J1") (pintype "bidirectional"))
    )
    (net (code "110") (name "/EEMR1_3_N") (class "Default")
      (node (ref "R200") (pin "1") (pinfunction "1_1") (pintype "passive"))
      (node (ref "U1") (pin "H3") (pinfunction "IOL_9A_H3") (pintype "bidirectional"))
    )
    (net (code "111") (name "/EEMR1_3_P") (class "Default")
      (node (ref "R203") (pin "1") (pinfunction "1_1") (pintype "passive"))
      (node (ref "U1") (pin "F2") (pinfunction "IOL_9B_F2") (pintype "bidirectional"))
    )
    (net (code "112") (name "/EEMR1_4_N") (class "Default")
      (node (ref "R208") (pin "1") (pinfunction "1_1") (pintype "passive"))
      (node (ref "U1") (pin "H5") (pinfunction "IOL_7A_H5") (pintype "bidirectional"))
    )
    (net (code "113") (name "/EEMR1_4_P") (class "Default")
      (node (ref "R209") (pin "1") (pinfunction "1_1") (pintype "passive"))
      (node (ref "U1") (pin "E2") (pinfunction "IOL_7B_E2") (pintype "bidirectional"))
    )
    (net (code "114") (name "/EEMR1_5_N") (class "Default")
      (node (ref "R210") (pin "1") (pinfunction "1_1") (pintype "passive"))
      (node (ref "U1") (pin "G5") (pinfunction "IOL_5A_G5") (pintype "bidirectional"))
    )
    (net (code "115") (name "/EEMR1_5_P") (class "Default")
      (node (ref "R211") (pin "1") (pinfunction "1_1") (pintype "passive"))
      (node (ref "U1") (pin "D1") (pinfunction "IOL_5B_D1") (pintype "bidirectional"))
    )
    (net (code "116") (name "/EEMR1_6_N") (class "Default")
      (node (ref "R212") (pin "1") (pinfunction "1_1") (pintype "passive"))
      (node (ref "U1") (pin "C1") (pinfunction "IOL_3A_C1") (pintype "bidirectional"))
    )
    (net (code "117") (name "/EEMR1_6_P") (class "Default")
      (node (ref "R213") (pin "1") (pinfunction "1_1") (pintype "passive"))
      (node (ref "U1") (pin "C2") (pinfunction "IOL_3B_C2") (pintype "bidirectional"))
    )
    (net (code "118") (name "/EEMR1_7_N") (class "Default")
      (node (ref "R214") (pin "1") (pinfunction "1_1") (pintype "passive"))
      (node (ref "U1") (pin "F5") (pinfunction "IOL_2A_F5") (pintype "bidirectional"))
    )
    (net (code "119") (name "/EEMR1_7_P") (class "Default")
      (node (ref "R215") (pin "1") (pinfunction "1_1") (pintype "passive"))
      (node (ref "U1") (pin "B1") (pinfunction "IOL_2B_B1") (pintype "bidirectional"))
    )
    (net (code "120") (name "/I2C0_SCL") (class "Default")
      (node (ref "D1") (pin "3") (pinfunction "I/O2_3") (pintype "bidirectional"))
      (node (ref "IC15") (pin "6") (pinfunction "SCL_6") (pintype "input"))
      (node (ref "IC25") (pin "1") (pinfunction "Y_1") (pintype "bidirectional"))
      (node (ref "IC32") (pin "1") (pinfunction "SCL_1") (pintype "input"))
      (node (ref "IC36") (pin "3") (pinfunction "Z_3") (pintype "bidirectional"))
      (node (ref "IC7") (pin "2") (pinfunction "SCL_2") (pintype "input"))
      (node (ref "J6") (pin "27") (pinfunction "27_27") (pintype "bidirectional"))
      (node (ref "R177") (pin "1") (pinfunction "1_1") (pintype "passive"))
      (node (ref "TP2") (pin "1") (pinfunction "1_1") (pintype "bidirectional"))
    )
    (net (code "121") (name "/I2C0_SDA") (class "Default")
      (node (ref "D1") (pin "2") (pinfunction "I/O1_2") (pintype "bidirectional"))
      (node (ref "IC15") (pin "5") (pinfunction "SDA_5") (pintype "bidirectional"))
      (node (ref "IC25") (pin "4") (pinfunction "Y_4") (pintype "bidirectional"))
      (node (ref "IC32") (pin "3") (pinfunction "SDA_3") (pintype "bidirectional"))
      (node (ref "IC36") (pin "2") (pinfunction "Z_2") (pintype "bidirectional"))
      (node (ref "IC7") (pin "1") (pinfunction "SDA_1") (pintype "bidirectional"))
      (node (ref "J6") (pin "26") (pinfunction "26_26") (pintype "bidirectional"))
      (node (ref "R175") (pin "1") (pinfunction "1_1") (pintype "passive"))
      (node (ref "TP1") (pin "1") (pinfunction "1_1") (pintype "bidirectional"))
    )
    (net (code "122") (name "/I2C1_SCL") (class "Default")
      (node (ref "D2") (pin "3") (pinfunction "I/O2_3") (pintype "bidirectional"))
      (node (ref "IC16") (pin "6") (pinfunction "SCL_6") (pintype "input"))
      (node (ref "IC36") (pin "9") (pinfunction "Z_9") (pintype "bidirectional"))
      (node (ref "IC9") (pin "1") (pinfunction "SCL_1") (pintype "input"))
      (node (ref "J10") (pin "27") (pinfunction "27_27") (pintype "bidirectional"))
      (node (ref "R87") (pin "1") (pinfunction "1_1") (pintype "passive"))
      (node (ref "TP12") (pin "1") (pinfunction "1_1") (pintype "bidirectional"))
    )
    (net (code "123") (name "/I2C1_SDA") (class "Default")
      (node (ref "D2") (pin "2") (pinfunction "I/O1_2") (pintype "bidirectional"))
      (node (ref "IC16") (pin "5") (pinfunction "SDA_5") (pintype "bidirectional"))
      (node (ref "IC36") (pin "10") (pinfunction "Z_10") (pintype "bidirectional"))
      (node (ref "IC9") (pin "3") (pinfunction "SDA_3") (pintype "bidirectional"))
      (node (ref "J10") (pin "26") (pinfunction "26_26") (pintype "bidirectional"))
      (node (ref "R88") (pin "1") (pinfunction "1_1") (pintype "passive"))
      (node (ref "TP6") (pin "1") (pinfunction "1_1") (pintype "bidirectional"))
    )
    (net (code "124") (name "/LED_ERR") (class "Default")
      (node (ref "LD19") (pin "1") (pinfunction "C_1") (pintype "passive"))
      (node (ref "R30") (pin "1") (pinfunction "1_1") (pintype "passive"))
    )
    (net (code "125") (name "/LED_OVT") (class "Default")
      (node (ref "IC7") (pin "3") (pinfunction "O.S._3") (pintype "output"))
      (node (ref "LD20") (pin "1") (pinfunction "C_1") (pintype "passive"))
      (node (ref "R89") (pin "1") (pinfunction "1_1") (pintype "passive"))
    )
    (net (code "126") (name "/LED_RED") (class "Default")
      (node (ref "T16") (pin "1") (pinfunction "G_1") (pintype "passive"))
      (node (ref "U1") (pin "F1") (pinfunction "IOL_10B_F1") (pintype "bidirectional"))
    )
    (net (code "127") (name "/PWR_EN") (class "Default")
      (node (ref "R86") (pin "2") (pinfunction "2_2") (pintype "passive"))
      (node (ref "R89") (pin "2") (pinfunction "2_2") (pintype "passive"))
    )
    (net (code "128") (name "/SERVMOD_3V3") (class "Default")
      (node (ref "IC25") (pin "13") (pinfunction "E_13") (pintype "input"))
      (node (ref "IC25") (pin "5") (pinfunction "E_5") (pintype "input"))
    )
    (net (code "129") (name "/Switch_I2C.SCL") (class "Default")
      (node (ref "IC25") (pin "2") (pinfunction "Z_2") (pintype "bidirectional"))
      (node (ref "R233") (pin "2") (pinfunction "2_2") (pintype "passive"))
    )
    (net (code "130") (name "/Switch_I2C.SDA") (class "Default")
      (node (ref "IC25") (pin "3") (pinfunction "Z_3") (pintype "bidirectional"))
      (node (ref "R3") (pin "2") (pinfunction "2_2") (pintype "passive"))
    )
    (net (code "135") (name "GND") (class "Default")
      (node (ref "C105") (pin "1") (pinfunction "1_1") (pintype "passive"))
      (node (ref "C113") (pin "2") (pinfunction "2_2") (pintype "passive"))
      (node (ref "C20") (pin "1") (pinfunction "1_1") (pintype "passive"))
      (node (ref "C38") (pin "1") (pinfunction "1_1") (pintype "passive"))
      (node (ref "C47") (pin "1") (pinfunction "1_1") (pintype "passive"))
      (node (ref "D1") (pin "1") (pinfunction "GND_1") (pintype "power_in"))
      (node (ref "D2") (pin "1") (pinfunction "GND_1") (pintype "power_in"))
      (node (ref "IC15") (pin "4") (pinfunction "VSS_4") (pintype "power_in"))
      (node (ref "IC16") (pin "4") (pinfunction "VSS_4") (pintype "power_in"))
      (node (ref "IC25") (pin "10") (pinfunction "Z_10") (pintype "bidirectional"))
      (node (ref "IC25") (pin "11") (pinfunction "Y_11") (pintype "bidirectional"))
      (node (ref "IC25") (pin "12") (pinfunction "E_12") (pintype "input"))
      (node (ref "IC25") (pin "6") (pinfunction "E_6") (pintype "input"))
      (node (ref "IC25") (pin "7") (pinfunction "GND_7") (pintype "power_in"))
      (node (ref "IC25") (pin "8") (pinfunction "Y_8") (pintype "bidirectional"))
      (node (ref "IC25") (pin "9") (pinfunction "Z_9") (pintype "bidirectional"))
      (node (ref "IC32") (pin "2") (pinfunction "VSS_2") (pintype "power_in"))
      (node (ref "IC36") (pin "7") (pinfunction "GND_7") (pintype "power_in"))
      (node (ref "IC7") (pin "4") (pinfunction "GND_4") (pintype "power_in"))
      (node (ref "IC9") (pin "2") (pinfunction "VSS_2") (pintype "power_in"))
      (node (ref "J10") (pin "1") (pinfunction "1_1") (pintype "bidirectional"))
      (node (ref "J10") (pin "10") (pinfunction "10_10") (pintype "bidirectional"))
      (node (ref "J10") (pin "13") (pinfunction "13_13") (pintype "bidirectional"))
      (node (ref "J10") (pin "16") (pinfunction "16_16") (pintype "bidirectional"))
      (node (ref "J10") (pin "19") (pinfunction "19_19") (pintype "bidirectional"))
      (node (ref "J10") (pin "22") (pinfunction "22_22") (pintype "bidirectional"))
      (node (ref "J10") (pin "25") (pinfunction "25_25") (pintype "bidirectional"))
      (node (ref "J10") (pin "4") (pinfunction "4_4") (pintype "bidirectional"))
      (node (ref "J10") (pin "7") (pinfunction "7_7") (pintype "bidirectional"))
      (node (ref "J6") (pin "1") (pinfunction "1_1") (pintype "bidirectional"))
      (node (ref "J6") (pin "10") (pinfunction "10_10") (pintype "bidirectional"))
      (node (ref "J6") (pin "13") (pinfunction "13_13") (pintype "bidirectional"))
      (node (ref "J6") (pin "16") (pinfunction "16_16") (pintype "bidirectional"))
      (node (ref "J6") (pin "19") (pinfunction "19_19") (pintype "bidirectional"))
      (node (ref "J6") (pin "22") (pinfunction "22_22") (pintype "bidirectional"))
      (node (ref "J6") (pin "25") (pinfunction "25_25") (pintype "bidirectional"))
      (node (ref "J6") (pin "4") (pinfunction "4_4") (pintype "bidirectional"))
      (node (ref "J6") (pin "7") (pinfunction "7_7") (pintype "bidirectional"))
      (node (ref "R90") (pin "1") (pinfunction "1_1") (pintype "passive"))
      (node (ref "R91") (pin "1") (pinfunction "1_1") (pintype "passive"))
      (node (ref "R92") (pin "1") (pinfunction "1_1") (pintype "passive"))
      (node (ref "T16") (pin "2") (pinfunction "S_2") (pintype "passive"))
    )
    (net (code "136") (name "Net-(IC7-A0)") (class "Default")
      (node (ref "IC7") (pin "7") (pinfunction "A0_7") (pintype "input"))
      (node (ref "R92") (pin "2") (pinfunction "2_2") (pintype "passive"))
    )
    (net (code "137") (name "Net-(IC7-A1)") (class "Default")
      (node (ref "IC7") (pin "6") (pinfunction "A1_6") (pintype "input"))
      (node (ref "R91") (pin "2") (pinfunction "2_2") (pintype "passive"))
    )
    (net (code "138") (name "Net-(IC7-A2)") (class "Default")
      (node (ref "IC7") (pin "5") (pinfunction "A2_5") (pintype "input"))
      (node (ref "R90") (pin "2") (pinfunction "2_2") (pintype "passive"))
    )
    (net (code "139") (name "Net-(IC36A-E)") (class "Default")
      (node (ref "IC36") (pin "12") (pinfunction "E_12") (pintype "input"))
      (node (ref "IC36") (pin "13") (pinfunction "E_13") (pintype "input"))
      (node (ref "IC36") (pin "5") (pinfunction "E_5") (pintype "input"))
      (node (ref "IC36") (pin "6") (pinfunction "E_6") (pintype "input"))
    )
    (net (code "140") (name "Net-(IC36A-Y)") (class "Default")
      (node (ref "IC36") (pin "1") (pinfunction "Y_1") (pintype "bidirectional"))
      (node (ref "R78") (pin "2") (pinfunction "2_2") (pintype "passive"))
    )
    (net (code "141") (name "Net-(IC36B-Y)") (class "Default")
      (node (ref "IC36") (pin "4") (pinfunction "Y_4") (pintype "bidirectional"))
      (node (ref "R74") (pin "2") (pinfunction "2_2") (pintype "passive"))
    )
    (net (code "142") (name "Net-(IC36C-Y)") (class "Default")
      (node (ref "IC36") (pin "8") (pinfunction "Y_8") (pintype "bidirectional"))
      (node (ref "R110") (pin "2") (pinfunction "2_2") (pintype "passive"))
    )
    (net (code "143") (name "Net-(IC36D-Y)") (class "Default")
      (node (ref "IC36") (pin "11") (pinfunction "Y_11") (pintype "bidirectional"))
      (node (ref "R84") (pin "2") (pinfunction "2_2") (pintype "passive"))
    )
    (net (code "144") (name "Net-(LD20-A)") (class "Default")
      (node (ref "LD20") (pin "2") (pinfunction "A_2") (pintype "passive"))
      (node (ref "R93") (pin "1") (pinfunction "1_1") (pintype "passive"))
    )
    (net (code "145") (name "Net-(T16-D)") (class "Default")
      (node (ref "R30") (pin "2") (pinfunction "2_2") (pintype "passive"))
      (node (ref "T16") (pin "3") (pinfunction "D_3") (pintype "passive"))
    )
    (net (code "146") (name "P3V3") (class "Default")
      (node (ref "R110") (pin "1") (pinfunction "1_1") (pintype "passive"))
      (node (ref "R74") (pin "1") (pinfunction "1_1") (pintype "passive"))
      (node (ref "R78") (pin "1") (pinfunction "1_1") (pintype "passive"))
      (node (ref "R84") (pin "1") (pinfunction "1_1") (pintype "passive"))
    )
    (net (code "147") (name "P3V3A") (class "Default")
      (node (ref "LD19") (pin "2") (pinfunction "A_2") (pintype "passive"))
    )
    (net (code "148") (name "P3V3_MP") (class "Default")
      (node (ref "C105") (pin "2") (pinfunction "2_2") (pintype "passive"))
      (node (ref "C113") (pin "1") (pinfunction "1_1") (pintype "passive"))
      (node (ref "C20") (pin "2") (pinfunction "2_2") (pintype "passive"))
      (node (ref "C38") (pin "2") (pinfunction "2_2") (pintype "passive"))
      (node (ref "C47") (pin "2") (pinfunction "2_2") (pintype "passive"))
      (node (ref "D1") (pin "4") (pinfunction "VCC_4") (pintype "power_in"))
      (node (ref "D2") (pin "4") (pinfunction "VCC_4") (pintype "power_in"))
      (node (ref "IC15") (pin "8") (pinfunction "VCC_8") (pintype "power_in"))
      (node (ref "IC16") (pin "8") (pinfunction "VCC_8") (pintype "power_in"))
      (node (ref "IC25") (pin "14") (pinfunction "VCC_14") (pintype "power_in"))
      (node (ref "IC32") (pin "4") (pinfunction "VCC_4") (pintype "power_in"))
      (node (ref "IC36") (pin "14") (pinfunction "VCC_14") (pintype "power_in"))
      (node (ref "IC7") (pin "8") (pinfunction "+VS_8") (pintype "power_in"))
      (node (ref "IC9") (pin "4") (pinfunction "VCC_4") (pintype "power_in"))
      (node (ref "J10") (pin "30") (pinfunction "30_30") (pintype "bidirectional"))
      (node (ref "J6") (pin "30") (pinfunction "30_30") (pintype "bidirectional"))
      (node (ref "R175") (pin "2") (pinfunction "2_2") (pintype "passive"))
      (node (ref "R177") (pin "2") (pinfunction "2_2") (pintype "passive"))
      (node (ref "R86") (pin "1") (pinfunction "1_1") (pintype "passive"))
      (node (ref "R87") (pin "2") (pinfunction "2_2") (pintype "passive"))
      (node (ref "R88") (pin "2") (pinfunction "2_2") (pintype "passive"))
      (node (ref "R93") (pin "2") (pinfunction "2_2") (pintype "passive"))
    )
    (net (code "149") (name "P12V0") (class "Default")
      (node (ref "J10") (pin "28") (pinfunction "28_28") (pintype "bidirectional"))
      (node (ref "J10") (pin "29") (pinfunction "29_29") (pintype "bidirectional"))
      (node (ref "J6") (pin "28") (pinfunction "28_28") (pintype "bidirectional"))
      (node (ref "J6") (pin "29") (pinfunction "29_29") (pintype "bidirectional"))
      (node (ref "R268") (pin "2") (pinfunction "2_2") (pintype "passive"))
      (node (ref "R269") (pin "2") (pinfunction "2_2") (pintype "passive"))
      (node (ref "R270") (pin "2") (pinfunction "2_2") (pintype "passive"))
      (node (ref "R271") (pin "2") (pinfunction "2_2") (pintype "passive"))
    )
    (net (code "150") (name "P12V0_CPCIS") (class "Default")
      (node (ref "R268") (pin "1") (pinfunction "1_1") (pintype "passive"))
      (node (ref "R269") (pin "1") (pinfunction "1_1") (pintype "passive"))
      (node (ref "R270") (pin "1") (pinfunction "1_1") (pintype "passive"))
      (node (ref "R271") (pin "1") (pinfunction "1_1") (pintype "passive"))
    )
    (net (code "151") (name "unconnected-(IC9-NC-Pad5)") (class "Default")
      (node (ref "IC9") (pin "5") (pinfunction "NC_5") (pintype "passive"))
    )
    (net (code "152") (name "unconnected-(IC15-A0_(NC)-Pad1)") (class "Default")
      (node (ref "IC15") (pin "1") (pinfunction "A0_(NC)_1") (pintype "input+no_connect"))
    )
    (net (code "153") (name "unconnected-(IC15-A1_(NC)-Pad2)") (class "Default")
      (node (ref "IC15") (pin "2") (pinfunction "A1_(NC)_2") (pintype "input+no_connect"))
    )
    (net (code "154") (name "unconnected-(IC15-A2_(NC)-Pad3)") (class "Default")
      (node (ref "IC15") (pin "3") (pinfunction "A2_(NC)_3") (pintype "input+no_connect"))
    )
    (net (code "155") (name "unconnected-(IC15-NC-Pad7)") (class "Default")
      (node (ref "IC15") (pin "7") (pinfunction "NC_7") (pintype "passive"))
    )
    (net (code "156") (name "unconnected-(IC16-A0_(NC)-Pad1)") (class "Default")
      (node (ref "IC16") (pin "1") (pinfunction "A0_(NC)_1") (pintype "input+no_connect"))
    )
    (net (code "157") (name "unconnected-(IC16-A1_(NC)-Pad2)") (class "Default")
      (node (ref "IC16") (pin "2") (pinfunction "A1_(NC)_2") (pintype "input+no_connect"))
    )
    (net (code "158") (name "unconnected-(IC16-A2_(NC)-Pad3)") (class "Default")
      (node (ref "IC16") (pin "3") (pinfunction "A2_(NC)_3") (pintype "input+no_connect"))
    )
    (net (code "159") (name "unconnected-(IC16-NC-Pad7)") (class "Default")
      (node (ref "IC16") (pin "7") (pinfunction "NC_7") (pintype "passive"))
    )
    (net (code "160") (name "unconnected-(IC32-NC-Pad5)") (class "Default")
      (node (ref "IC32") (pin "5") (pinfunction "NC_5") (pintype "passive"))
    )
    (net (code "161") (name "unconnected-(U1D-IOL_8A-PadG3)") (class "Default")
      (node (ref "U1") (pin "G3") (pinfunction "IOL_8A_G3") (pintype "bidirectional+no_connect"))
    )
    (net (code "162") (name "unconnected-(U1D-IOL_8B-PadF3)") (class "Default")
      (node (ref "U1") (pin "F3") (pinfunction "IOL_8B_F3") (pintype "bidirectional+no_connect"))
    )
    (net (code "163") (name "unconnected-(U1D-IOL_10A-PadH6)") (class "Default")
      (node (ref "U1") (pin "H6") (pinfunction "IOL_10A_H6") (pintype "bidirectional+no_connect"))
    )
  )
)
